# 10-de-77.net
KiCad netlist of a schematic drawn in EAGLE
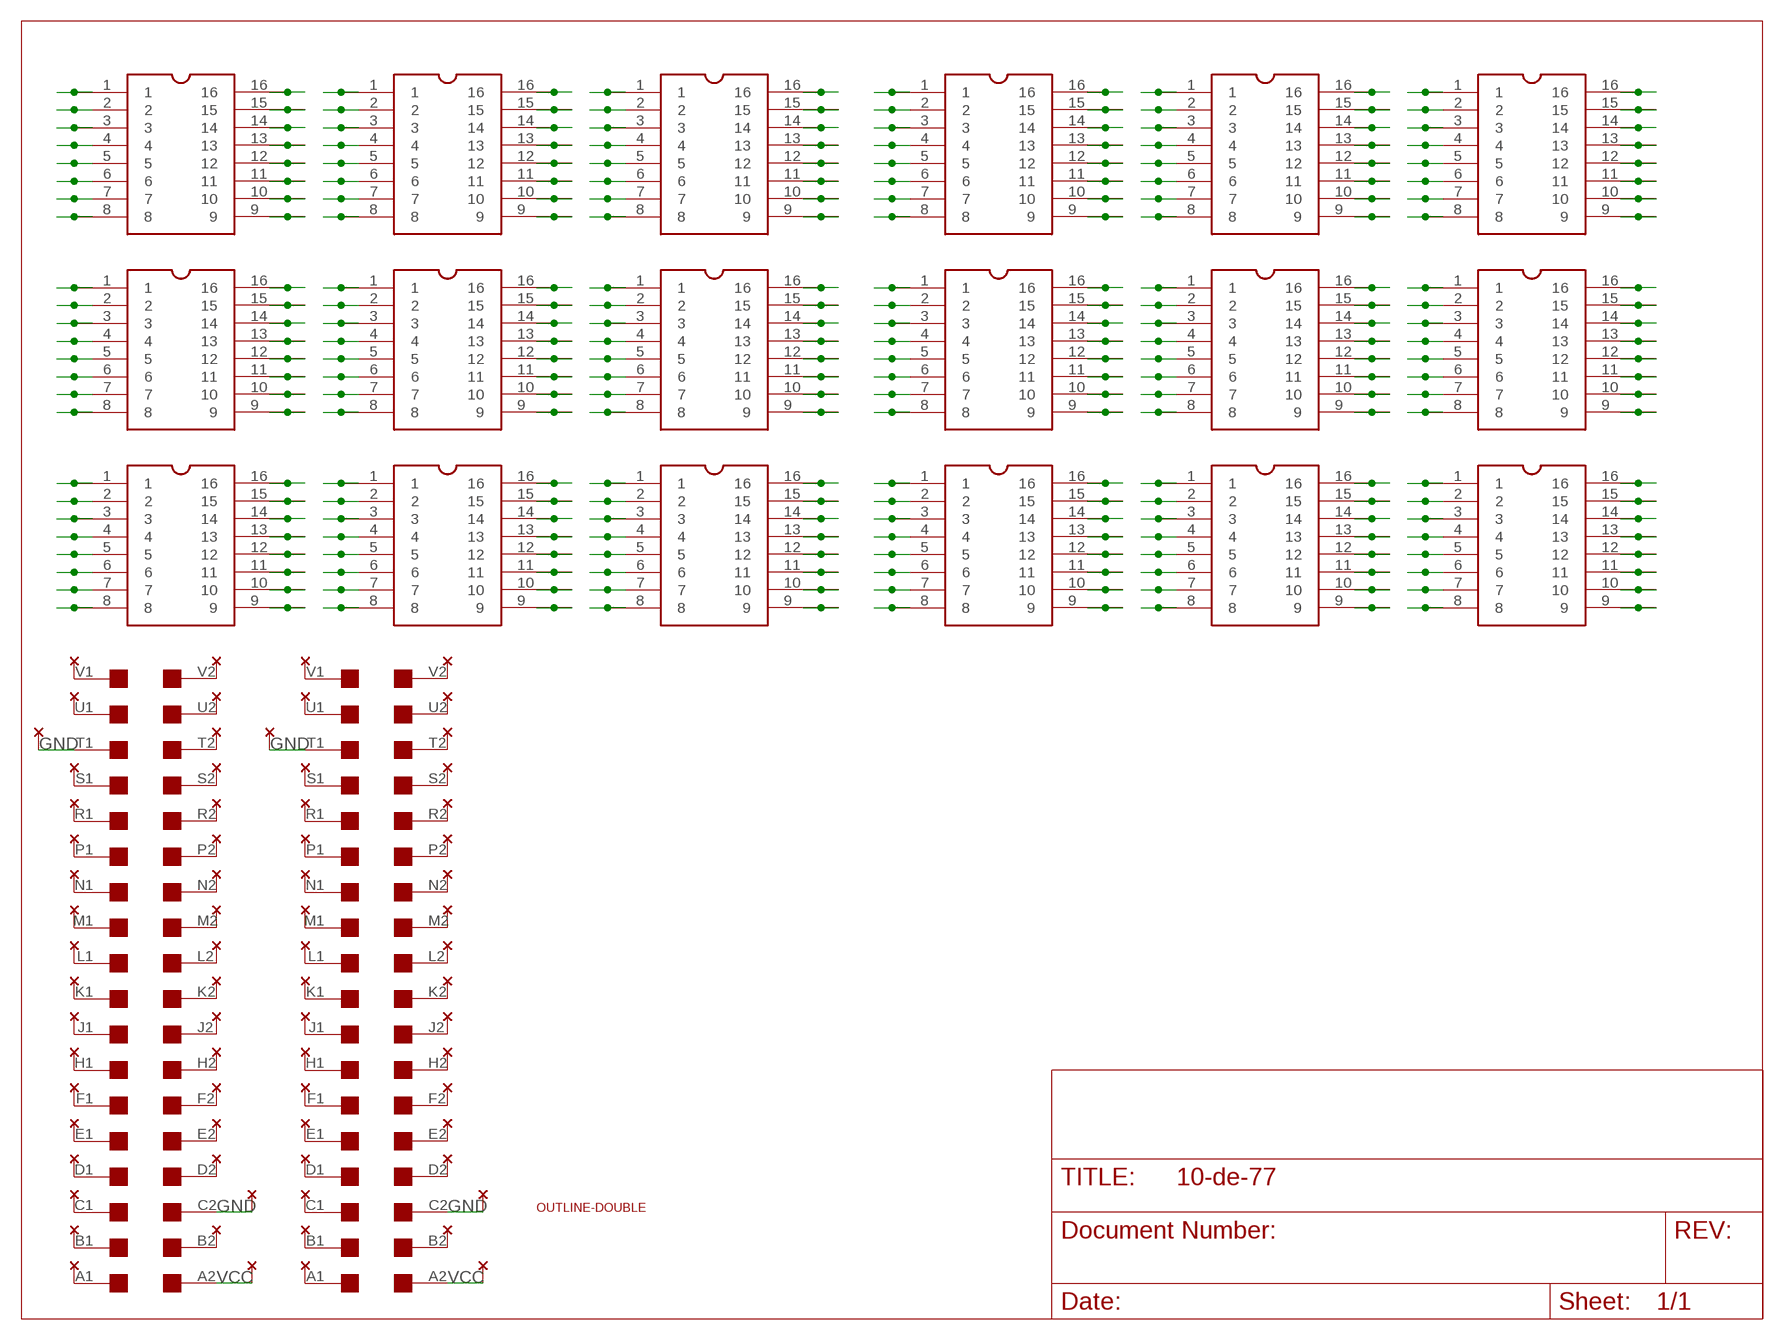
[diagram p0: schematic, sheet 1]

(export (version "E")
  (design (tool "Eeschema 10.0.6"))
  (components
    (comp (ref "U$1")
      (value "SINGLE")
      (footprint "eagle-import:EDGE-CON2")
      (libsource (lib "eagle-import") (part "SINGLE"))
    )
    (comp (ref "U$4")
      (value "OUTLINE-DOUBLE")
      (footprint "eagle-import:DOUBLE")
      (libsource (lib "eagle-import") (part "OUTLINE-DOUBLE"))
    )
    (comp (ref "U$5")
      (value "DIL16PROTO")
      (footprint "eagle-import:DIL16PROTO")
      (libsource (lib "eagle-import") (part "DIL16PROTO"))
    )
    (comp (ref "U$6")
      (value "SINGLE")
      (footprint "eagle-import:EDGE-CON2")
      (libsource (lib "eagle-import") (part "SINGLE"))
    )
    (comp (ref "U$7")
      (value "DIL16PROTO")
      (footprint "eagle-import:DIL16PROTO")
      (libsource (lib "eagle-import") (part "DIL16PROTO"))
    )
    (comp (ref "U$8")
      (value "DIL16PROTO")
      (footprint "eagle-import:DIL16PROTO")
      (libsource (lib "eagle-import") (part "DIL16PROTO"))
    )
    (comp (ref "U$9")
      (value "DIL16PROTO")
      (footprint "eagle-import:DIL16PROTO")
      (libsource (lib "eagle-import") (part "DIL16PROTO"))
    )
    (comp (ref "U$10")
      (value "DIL16PROTO")
      (footprint "eagle-import:DIL16PROTO")
      (libsource (lib "eagle-import") (part "DIL16PROTO"))
    )
    (comp (ref "U$11")
      (value "DIL16PROTO")
      (footprint "eagle-import:DIL16PROTO")
      (libsource (lib "eagle-import") (part "DIL16PROTO"))
    )
    (comp (ref "U$12")
      (value "DIL16PROTO")
      (footprint "eagle-import:DIL16PROTO")
      (libsource (lib "eagle-import") (part "DIL16PROTO"))
    )
    (comp (ref "U$13")
      (value "DIL16PROTO")
      (footprint "eagle-import:DIL16PROTO")
      (libsource (lib "eagle-import") (part "DIL16PROTO"))
    )
    (comp (ref "U$14")
      (value "DIL16PROTO")
      (footprint "eagle-import:DIL16PROTO")
      (libsource (lib "eagle-import") (part "DIL16PROTO"))
    )
    (comp (ref "U$15")
      (value "DIL16PROTO")
      (footprint "eagle-import:DIL16PROTO")
      (libsource (lib "eagle-import") (part "DIL16PROTO"))
    )
    (comp (ref "U$16")
      (value "DIL16PROTO")
      (footprint "eagle-import:DIL16PROTO")
      (libsource (lib "eagle-import") (part "DIL16PROTO"))
    )
    (comp (ref "U$17")
      (value "DIL16PROTO")
      (footprint "eagle-import:DIL16PROTO")
      (libsource (lib "eagle-import") (part "DIL16PROTO"))
    )
    (comp (ref "U$18")
      (value "DIL16PROTO")
      (footprint "eagle-import:DIL16PROTO")
      (libsource (lib "eagle-import") (part "DIL16PROTO"))
    )
    (comp (ref "U$19")
      (value "DIL16PROTO")
      (footprint "eagle-import:DIL16PROTO")
      (libsource (lib "eagle-import") (part "DIL16PROTO"))
    )
    (comp (ref "U$20")
      (value "DIL16PROTO")
      (footprint "eagle-import:DIL16PROTO")
      (libsource (lib "eagle-import") (part "DIL16PROTO"))
    )
    (comp (ref "U$21")
      (value "DIL16PROTO")
      (footprint "eagle-import:DIL16PROTO")
      (libsource (lib "eagle-import") (part "DIL16PROTO"))
    )
    (comp (ref "U$22")
      (value "DIL16PROTO")
      (footprint "eagle-import:DIL16PROTO")
      (libsource (lib "eagle-import") (part "DIL16PROTO"))
    )
    (comp (ref "U$23")
      (value "DIL16PROTO")
      (footprint "eagle-import:DIL16PROTO")
      (libsource (lib "eagle-import") (part "DIL16PROTO"))
    )
    (comp (ref "U$24")
      (value "THRU-HOLE1A")
      (footprint "eagle-import:THRU-HOLE1A")
      (libsource (lib "eagle-import") (part "THRU-HOLE1A"))
    )
    (comp (ref "U$25")
      (value "THRU-HOLE1A")
      (footprint "eagle-import:THRU-HOLE1A")
      (libsource (lib "eagle-import") (part "THRU-HOLE1A"))
    )
    (comp (ref "U$26")
      (value "THRU-HOLE1A")
      (footprint "eagle-import:THRU-HOLE1A")
      (libsource (lib "eagle-import") (part "THRU-HOLE1A"))
    )
    (comp (ref "U$27")
      (value "THRU-HOLE1A")
      (footprint "eagle-import:THRU-HOLE1A")
      (libsource (lib "eagle-import") (part "THRU-HOLE1A"))
    )
  )
  (nets
    (net (code "1") (name "/GND") (class "Default")
      (node (ref "U$1") (pin "C2") (pinfunction "1_C2") (pintype "bidirectional"))
      (node (ref "U$1") (pin "T1") (pinfunction "1_T1") (pintype "bidirectional"))
      (node (ref "U$24") (pin "T1") (pinfunction "P$1_T1") (pintype "passive"))
      (node (ref "U$25") (pin "C1") (pinfunction "P$1_C1") (pintype "passive"))
      (node (ref "U$26") (pin "T1") (pinfunction "P$1_T1") (pintype "passive"))
      (node (ref "U$27") (pin "C1") (pinfunction "P$1_C1") (pintype "passive"))
      (node (ref "U$6") (pin "C2") (pinfunction "1_C2") (pintype "bidirectional"))
      (node (ref "U$6") (pin "T1") (pinfunction "1_T1") (pintype "bidirectional"))
    )
    (net (code "2") (name "/VCC") (class "Default")
      (node (ref "U$1") (pin "A2") (pinfunction "1_A2") (pintype "bidirectional"))
      (node (ref "U$25") (pin "A1") (pinfunction "P$1_A1") (pintype "passive"))
      (node (ref "U$27") (pin "A1") (pinfunction "P$1_A1") (pintype "passive"))
      (node (ref "U$6") (pin "A2") (pinfunction "1_A2") (pintype "bidirectional"))
    )
    (net (code "3") (name "Net-(U$1A-1)") (class "Default")
      (node (ref "U$1") (pin "A1") (pinfunction "1_A1") (pintype "bidirectional"))
      (node (ref "U$24") (pin "A1") (pinfunction "P$1_A1") (pintype "passive"))
    )
    (net (code "4") (name "Net-(U$1AA-1)") (class "Default")
      (node (ref "U$1") (pin "R1") (pinfunction "1_R1") (pintype "bidirectional"))
      (node (ref "U$24") (pin "R1") (pinfunction "P$1_R1") (pintype "passive"))
    )
    (net (code "5") (name "Net-(U$1AB-1)") (class "Default")
      (node (ref "U$1") (pin "R2") (pinfunction "1_R2") (pintype "bidirectional"))
      (node (ref "U$25") (pin "R1") (pinfunction "P$1_R1") (pintype "passive"))
    )
    (net (code "6") (name "Net-(U$1AC-1)") (class "Default")
      (node (ref "U$1") (pin "S1") (pinfunction "1_S1") (pintype "bidirectional"))
      (node (ref "U$24") (pin "S1") (pinfunction "P$1_S1") (pintype "passive"))
    )
    (net (code "7") (name "Net-(U$1AD-1)") (class "Default")
      (node (ref "U$1") (pin "S2") (pinfunction "1_S2") (pintype "bidirectional"))
      (node (ref "U$25") (pin "S1") (pinfunction "P$1_S1") (pintype "passive"))
    )
    (net (code "8") (name "Net-(U$1AF-1)") (class "Default")
      (node (ref "U$1") (pin "T2") (pinfunction "1_T2") (pintype "bidirectional"))
      (node (ref "U$25") (pin "T1") (pinfunction "P$1_T1") (pintype "passive"))
    )
    (net (code "9") (name "Net-(U$1AG-1)") (class "Default")
      (node (ref "U$1") (pin "U1") (pinfunction "1_U1") (pintype "bidirectional"))
      (node (ref "U$24") (pin "U1") (pinfunction "P$1_U1") (pintype "passive"))
    )
    (net (code "10") (name "Net-(U$1AH-1)") (class "Default")
      (node (ref "U$1") (pin "U2") (pinfunction "1_U2") (pintype "bidirectional"))
      (node (ref "U$25") (pin "U1") (pinfunction "P$1_U1") (pintype "passive"))
    )
    (net (code "11") (name "Net-(U$1AI-1)") (class "Default")
      (node (ref "U$1") (pin "V1") (pinfunction "1_V1") (pintype "bidirectional"))
      (node (ref "U$24") (pin "V1") (pinfunction "P$1_V1") (pintype "passive"))
    )
    (net (code "12") (name "Net-(U$1AJ-1)") (class "Default")
      (node (ref "U$1") (pin "V2") (pinfunction "1_V2") (pintype "bidirectional"))
      (node (ref "U$25") (pin "V1") (pinfunction "P$1_V1") (pintype "passive"))
    )
    (net (code "13") (name "Net-(U$1C-1)") (class "Default")
      (node (ref "U$1") (pin "B1") (pinfunction "1_B1") (pintype "bidirectional"))
      (node (ref "U$24") (pin "B1") (pinfunction "P$1_B1") (pintype "passive"))
    )
    (net (code "14") (name "Net-(U$1D-1)") (class "Default")
      (node (ref "U$1") (pin "B2") (pinfunction "1_B2") (pintype "bidirectional"))
      (node (ref "U$25") (pin "B1") (pinfunction "P$1_B1") (pintype "passive"))
    )
    (net (code "15") (name "Net-(U$1E-1)") (class "Default")
      (node (ref "U$1") (pin "C1") (pinfunction "1_C1") (pintype "bidirectional"))
      (node (ref "U$24") (pin "C1") (pinfunction "P$1_C1") (pintype "passive"))
    )
    (net (code "16") (name "Net-(U$1G-1)") (class "Default")
      (node (ref "U$1") (pin "D1") (pinfunction "1_D1") (pintype "bidirectional"))
      (node (ref "U$24") (pin "D1") (pinfunction "P$1_D1") (pintype "passive"))
    )
    (net (code "17") (name "Net-(U$1H-1)") (class "Default")
      (node (ref "U$1") (pin "D2") (pinfunction "1_D2") (pintype "bidirectional"))
      (node (ref "U$25") (pin "D1") (pinfunction "P$1_D1") (pintype "passive"))
    )
    (net (code "18") (name "Net-(U$1I-1)") (class "Default")
      (node (ref "U$1") (pin "E1") (pinfunction "1_E1") (pintype "bidirectional"))
      (node (ref "U$24") (pin "E1") (pinfunction "P$1_E1") (pintype "passive"))
    )
    (net (code "19") (name "Net-(U$1J-1)") (class "Default")
      (node (ref "U$1") (pin "E2") (pinfunction "1_E2") (pintype "bidirectional"))
      (node (ref "U$25") (pin "E1") (pinfunction "P$1_E1") (pintype "passive"))
    )
    (net (code "20") (name "Net-(U$1K-1)") (class "Default")
      (node (ref "U$1") (pin "F1") (pinfunction "1_F1") (pintype "bidirectional"))
      (node (ref "U$24") (pin "F1") (pinfunction "P$1_F1") (pintype "passive"))
    )
    (net (code "21") (name "Net-(U$1L-1)") (class "Default")
      (node (ref "U$1") (pin "F2") (pinfunction "1_F2") (pintype "bidirectional"))
      (node (ref "U$25") (pin "F1") (pinfunction "P$1_F1") (pintype "passive"))
    )
    (net (code "22") (name "Net-(U$1M-1)") (class "Default")
      (node (ref "U$1") (pin "H1") (pinfunction "1_H1") (pintype "bidirectional"))
      (node (ref "U$24") (pin "H1") (pinfunction "P$1_H1") (pintype "passive"))
    )
    (net (code "23") (name "Net-(U$1N-1)") (class "Default")
      (node (ref "U$1") (pin "H2") (pinfunction "1_H2") (pintype "bidirectional"))
      (node (ref "U$25") (pin "H1") (pinfunction "P$1_H1") (pintype "passive"))
    )
    (net (code "24") (name "Net-(U$1O-1)") (class "Default")
      (node (ref "U$1") (pin "J1") (pinfunction "1_J1") (pintype "bidirectional"))
      (node (ref "U$24") (pin "J1") (pinfunction "P$1_J1") (pintype "passive"))
    )
    (net (code "25") (name "Net-(U$1P-1)") (class "Default")
      (node (ref "U$1") (pin "J2") (pinfunction "1_J2") (pintype "bidirectional"))
      (node (ref "U$25") (pin "J1") (pinfunction "P$1_J1") (pintype "passive"))
    )
    (net (code "26") (name "Net-(U$1Q-1)") (class "Default")
      (node (ref "U$1") (pin "K1") (pinfunction "1_K1") (pintype "bidirectional"))
      (node (ref "U$24") (pin "K1") (pinfunction "P$1_K1") (pintype "passive"))
    )
    (net (code "27") (name "Net-(U$1R-1)") (class "Default")
      (node (ref "U$1") (pin "K2") (pinfunction "1_K2") (pintype "bidirectional"))
      (node (ref "U$25") (pin "K1") (pinfunction "P$1_K1") (pintype "passive"))
    )
    (net (code "28") (name "Net-(U$1S-1)") (class "Default")
      (node (ref "U$1") (pin "L1") (pinfunction "1_L1") (pintype "bidirectional"))
      (node (ref "U$24") (pin "L1") (pinfunction "P$1_L1") (pintype "passive"))
    )
    (net (code "29") (name "Net-(U$1T-1)") (class "Default")
      (node (ref "U$1") (pin "L2") (pinfunction "1_L2") (pintype "bidirectional"))
      (node (ref "U$25") (pin "L1") (pinfunction "P$1_L1") (pintype "passive"))
    )
    (net (code "30") (name "Net-(U$1U-1)") (class "Default")
      (node (ref "U$1") (pin "M1") (pinfunction "1_M1") (pintype "bidirectional"))
      (node (ref "U$24") (pin "M1") (pinfunction "P$1_M1") (pintype "passive"))
    )
    (net (code "31") (name "Net-(U$1V-1)") (class "Default")
      (node (ref "U$1") (pin "M2") (pinfunction "1_M2") (pintype "bidirectional"))
      (node (ref "U$25") (pin "M1") (pinfunction "P$1_M1") (pintype "passive"))
    )
    (net (code "32") (name "Net-(U$1W-1)") (class "Default")
      (node (ref "U$1") (pin "N1") (pinfunction "1_N1") (pintype "bidirectional"))
      (node (ref "U$24") (pin "N1") (pinfunction "P$1_N1") (pintype "passive"))
    )
    (net (code "33") (name "Net-(U$1X-1)") (class "Default")
      (node (ref "U$1") (pin "N2") (pinfunction "1_N2") (pintype "bidirectional"))
      (node (ref "U$25") (pin "N1") (pinfunction "P$1_N1") (pintype "passive"))
    )
    (net (code "34") (name "Net-(U$1Y-1)") (class "Default")
      (node (ref "U$1") (pin "P1") (pinfunction "1_P1") (pintype "bidirectional"))
      (node (ref "U$24") (pin "P1") (pinfunction "P$1_P1") (pintype "passive"))
    )
    (net (code "35") (name "Net-(U$1Z-1)") (class "Default")
      (node (ref "U$1") (pin "P2") (pinfunction "1_P2") (pintype "bidirectional"))
      (node (ref "U$25") (pin "P1") (pinfunction "P$1_P1") (pintype "passive"))
    )
    (net (code "36") (name "Net-(U$5-1-Pad1@2)") (class "Default")
      (node (ref "U$5") (pin "1") (pinfunction "1_1") (pintype "passive"))
      (node (ref "U$5") (pin "1@2") (pinfunction "1_1@2") (pintype "passive"))
      (node (ref "U$5") (pin "1@3") (pinfunction "1_1@3") (pintype "passive"))
    )
    (net (code "37") (name "Net-(U$5-2-Pad2@2)") (class "Default")
      (node (ref "U$5") (pin "2") (pinfunction "2_2") (pintype "passive"))
      (node (ref "U$5") (pin "2@2") (pinfunction "2_2@2") (pintype "passive"))
      (node (ref "U$5") (pin "2@3") (pinfunction "2_2@3") (pintype "passive"))
    )
    (net (code "38") (name "Net-(U$5-3-Pad3@2)") (class "Default")
      (node (ref "U$5") (pin "3") (pinfunction "3_3") (pintype "passive"))
      (node (ref "U$5") (pin "3@2") (pinfunction "3_3@2") (pintype "passive"))
      (node (ref "U$5") (pin "3@3") (pinfunction "3_3@3") (pintype "passive"))
    )
    (net (code "39") (name "Net-(U$5-4-Pad4@2)") (class "Default")
      (node (ref "U$5") (pin "4") (pinfunction "4_4") (pintype "passive"))
      (node (ref "U$5") (pin "4@2") (pinfunction "4_4@2") (pintype "passive"))
      (node (ref "U$5") (pin "4@3") (pinfunction "4_4@3") (pintype "passive"))
    )
    (net (code "40") (name "Net-(U$5-5-Pad5@2)") (class "Default")
      (node (ref "U$5") (pin "5") (pinfunction "5_5") (pintype "passive"))
      (node (ref "U$5") (pin "5@2") (pinfunction "5_5@2") (pintype "passive"))
      (node (ref "U$5") (pin "5@3") (pinfunction "5_5@3") (pintype "passive"))
    )
    (net (code "41") (name "Net-(U$5-6-Pad6@2)") (class "Default")
      (node (ref "U$5") (pin "6") (pinfunction "6_6") (pintype "passive"))
      (node (ref "U$5") (pin "6@2") (pinfunction "6_6@2") (pintype "passive"))
      (node (ref "U$5") (pin "6@3") (pinfunction "6_6@3") (pintype "passive"))
    )
    (net (code "42") (name "Net-(U$5-7-Pad7@2)") (class "Default")
      (node (ref "U$5") (pin "7") (pinfunction "7_7") (pintype "passive"))
      (node (ref "U$5") (pin "7@2") (pinfunction "7_7@2") (pintype "passive"))
      (node (ref "U$5") (pin "7@3") (pinfunction "7_7@3") (pintype "passive"))
    )
    (net (code "43") (name "Net-(U$5-8-Pad8@2)") (class "Default")
      (node (ref "U$5") (pin "8") (pinfunction "8_8") (pintype "passive"))
      (node (ref "U$5") (pin "8@2") (pinfunction "8_8@2") (pintype "passive"))
      (node (ref "U$5") (pin "8@3") (pinfunction "8_8@3") (pintype "passive"))
    )
    (net (code "44") (name "Net-(U$5-9-Pad9@2)") (class "Default")
      (node (ref "U$5") (pin "9") (pinfunction "9_9") (pintype "passive"))
      (node (ref "U$5") (pin "9@2") (pinfunction "9_9@2") (pintype "passive"))
      (node (ref "U$5") (pin "9@3") (pinfunction "9_9@3") (pintype "passive"))
    )
    (net (code "45") (name "Net-(U$5-10-Pad10@2)") (class "Default")
      (node (ref "U$5") (pin "10") (pinfunction "10_10") (pintype "passive"))
      (node (ref "U$5") (pin "10@2") (pinfunction "10_10@2") (pintype "passive"))
      (node (ref "U$5") (pin "10@3") (pinfunction "10_10@3") (pintype "passive"))
    )
    (net (code "46") (name "Net-(U$5-11-Pad11@2)") (class "Default")
      (node (ref "U$5") (pin "11") (pinfunction "11_11") (pintype "passive"))
      (node (ref "U$5") (pin "11@2") (pinfunction "11_11@2") (pintype "passive"))
      (node (ref "U$5") (pin "11@3") (pinfunction "11_11@3") (pintype "passive"))
    )
    (net (code "47") (name "Net-(U$5-12-Pad12@2)") (class "Default")
      (node (ref "U$5") (pin "12") (pinfunction "12_12") (pintype "passive"))
      (node (ref "U$5") (pin "12@2") (pinfunction "12_12@2") (pintype "passive"))
      (node (ref "U$5") (pin "12@3") (pinfunction "12_12@3") (pintype "passive"))
    )
    (net (code "48") (name "Net-(U$5-13-Pad13@2)") (class "Default")
      (node (ref "U$5") (pin "13") (pinfunction "13_13") (pintype "passive"))
      (node (ref "U$5") (pin "13@2") (pinfunction "13_13@2") (pintype "passive"))
      (node (ref "U$5") (pin "13@3") (pinfunction "13_13@3") (pintype "passive"))
    )
    (net (code "49") (name "Net-(U$5-14-Pad14@2)") (class "Default")
      (node (ref "U$5") (pin "14") (pinfunction "14_14") (pintype "passive"))
      (node (ref "U$5") (pin "14@2") (pinfunction "14_14@2") (pintype "passive"))
      (node (ref "U$5") (pin "14@3") (pinfunction "14_14@3") (pintype "passive"))
    )
    (net (code "50") (name "Net-(U$5-15-Pad15@2)") (class "Default")
      (node (ref "U$5") (pin "15") (pinfunction "15_15") (pintype "passive"))
      (node (ref "U$5") (pin "15@2") (pinfunction "15_15@2") (pintype "passive"))
      (node (ref "U$5") (pin "15@3") (pinfunction "15_15@3") (pintype "passive"))
    )
    (net (code "51") (name "Net-(U$5-16-Pad16@2)") (class "Default")
      (node (ref "U$5") (pin "16") (pinfunction "16_16") (pintype "passive"))
      (node (ref "U$5") (pin "16@2") (pinfunction "16_16@2") (pintype "passive"))
      (node (ref "U$5") (pin "16@3") (pinfunction "16_16@3") (pintype "passive"))
    )
    (net (code "52") (name "Net-(U$7-1-Pad1@2)") (class "Default")
      (node (ref "U$7") (pin "1") (pinfunction "1_1") (pintype "passive"))
      (node (ref "U$7") (pin "1@2") (pinfunction "1_1@2") (pintype "passive"))
      (node (ref "U$7") (pin "1@3") (pinfunction "1_1@3") (pintype "passive"))
    )
    (net (code "53") (name "Net-(U$7-2-Pad2@2)") (class "Default")
      (node (ref "U$7") (pin "2") (pinfunction "2_2") (pintype "passive"))
      (node (ref "U$7") (pin "2@2") (pinfunction "2_2@2") (pintype "passive"))
      (node (ref "U$7") (pin "2@3") (pinfunction "2_2@3") (pintype "passive"))
    )
    (net (code "54") (name "Net-(U$7-3-Pad3@2)") (class "Default")
      (node (ref "U$7") (pin "3") (pinfunction "3_3") (pintype "passive"))
      (node (ref "U$7") (pin "3@2") (pinfunction "3_3@2") (pintype "passive"))
      (node (ref "U$7") (pin "3@3") (pinfunction "3_3@3") (pintype "passive"))
    )
    (net (code "55") (name "Net-(U$7-4-Pad4@2)") (class "Default")
      (node (ref "U$7") (pin "4") (pinfunction "4_4") (pintype "passive"))
      (node (ref "U$7") (pin "4@2") (pinfunction "4_4@2") (pintype "passive"))
      (node (ref "U$7") (pin "4@3") (pinfunction "4_4@3") (pintype "passive"))
    )
    (net (code "56") (name "Net-(U$7-5-Pad5@2)") (class "Default")
      (node (ref "U$7") (pin "5") (pinfunction "5_5") (pintype "passive"))
      (node (ref "U$7") (pin "5@2") (pinfunction "5_5@2") (pintype "passive"))
      (node (ref "U$7") (pin "5@3") (pinfunction "5_5@3") (pintype "passive"))
    )
    (net (code "57") (name "Net-(U$7-6-Pad6@2)") (class "Default")
      (node (ref "U$7") (pin "6") (pinfunction "6_6") (pintype "passive"))
      (node (ref "U$7") (pin "6@2") (pinfunction "6_6@2") (pintype "passive"))
      (node (ref "U$7") (pin "6@3") (pinfunction "6_6@3") (pintype "passive"))
    )
    (net (code "58") (name "Net-(U$7-7-Pad7@2)") (class "Default")
      (node (ref "U$7") (pin "7") (pinfunction "7_7") (pintype "passive"))
      (node (ref "U$7") (pin "7@2") (pinfunction "7_7@2") (pintype "passive"))
      (node (ref "U$7") (pin "7@3") (pinfunction "7_7@3") (pintype "passive"))
    )
    (net (code "59") (name "Net-(U$7-8-Pad8@2)") (class "Default")
      (node (ref "U$7") (pin "8") (pinfunction "8_8") (pintype "passive"))
      (node (ref "U$7") (pin "8@2") (pinfunction "8_8@2") (pintype "passive"))
      (node (ref "U$7") (pin "8@3") (pinfunction "8_8@3") (pintype "passive"))
    )
    (net (code "60") (name "Net-(U$7-9-Pad9@2)") (class "Default")
      (node (ref "U$7") (pin "9") (pinfunction "9_9") (pintype "passive"))
      (node (ref "U$7") (pin "9@2") (pinfunction "9_9@2") (pintype "passive"))
      (node (ref "U$7") (pin "9@3") (pinfunction "9_9@3") (pintype "passive"))
    )
    (net (code "61") (name "Net-(U$7-10-Pad10@2)") (class "Default")
      (node (ref "U$7") (pin "10") (pinfunction "10_10") (pintype "passive"))
      (node (ref "U$7") (pin "10@2") (pinfunction "10_10@2") (pintype "passive"))
      (node (ref "U$7") (pin "10@3") (pinfunction "10_10@3") (pintype "passive"))
    )
    (net (code "62") (name "Net-(U$7-11-Pad11@2)") (class "Default")
      (node (ref "U$7") (pin "11") (pinfunction "11_11") (pintype "passive"))
      (node (ref "U$7") (pin "11@2") (pinfunction "11_11@2") (pintype "passive"))
      (node (ref "U$7") (pin "11@3") (pinfunction "11_11@3") (pintype "passive"))
    )
    (net (code "63") (name "Net-(U$7-12-Pad12@2)") (class "Default")
      (node (ref "U$7") (pin "12") (pinfunction "12_12") (pintype "passive"))
      (node (ref "U$7") (pin "12@2") (pinfunction "12_12@2") (pintype "passive"))
      (node (ref "U$7") (pin "12@3") (pinfunction "12_12@3") (pintype "passive"))
    )
    (net (code "64") (name "Net-(U$7-13-Pad13@2)") (class "Default")
      (node (ref "U$7") (pin "13") (pinfunction "13_13") (pintype "passive"))
      (node (ref "U$7") (pin "13@2") (pinfunction "13_13@2") (pintype "passive"))
      (node (ref "U$7") (pin "13@3") (pinfunction "13_13@3") (pintype "passive"))
    )
    (net (code "65") (name "Net-(U$7-14-Pad14@2)") (class "Default")
      (node (ref "U$7") (pin "14") (pinfunction "14_14") (pintype "passive"))
      (node (ref "U$7") (pin "14@2") (pinfunction "14_14@2") (pintype "passive"))
      (node (ref "U$7") (pin "14@3") (pinfunction "14_14@3") (pintype "passive"))
    )
    (net (code "66") (name "Net-(U$7-15-Pad15@2)") (class "Default")
      (node (ref "U$7") (pin "15") (pinfunction "15_15") (pintype "passive"))
      (node (ref "U$7") (pin "15@2") (pinfunction "15_15@2") (pintype "passive"))
      (node (ref "U$7") (pin "15@3") (pinfunction "15_15@3") (pintype "passive"))
    )
    (net (code "67") (name "Net-(U$7-16-Pad16@2)") (class "Default")
      (node (ref "U$7") (pin "16") (pinfunction "16_16") (pintype "passive"))
      (node (ref "U$7") (pin "16@2") (pinfunction "16_16@2") (pintype "passive"))
      (node (ref "U$7") (pin "16@3") (pinfunction "16_16@3") (pintype "passive"))
    )
    (net (code "68") (name "Net-(U$8-1-Pad1@2)") (class "Default")
      (node (ref "U$8") (pin "1") (pinfunction "1_1") (pintype "passive"))
      (node (ref "U$8") (pin "1@2") (pinfunction "1_1@2") (pintype "passive"))
      (node (ref "U$8") (pin "1@3") (pinfunction "1_1@3") (pintype "passive"))
    )
    (net (code "69") (name "Net-(U$8-2-Pad2@2)") (class "Default")
      (node (ref "U$8") (pin "2") (pinfunction "2_2") (pintype "passive"))
      (node (ref "U$8") (pin "2@2") (pinfunction "2_2@2") (pintype "passive"))
      (node (ref "U$8") (pin "2@3") (pinfunction "2_2@3") (pintype "passive"))
    )
    (net (code "70") (name "Net-(U$8-3-Pad3@2)") (class "Default")
      (node (ref "U$8") (pin "3") (pinfunction "3_3") (pintype "passive"))
      (node (ref "U$8") (pin "3@2") (pinfunction "3_3@2") (pintype "passive"))
      (node (ref "U$8") (pin "3@3") (pinfunction "3_3@3") (pintype "passive"))
    )
    (net (code "71") (name "Net-(U$8-4-Pad4@2)") (class "Default")
      (node (ref "U$8") (pin "4") (pinfunction "4_4") (pintype "passive"))
      (node (ref "U$8") (pin "4@2") (pinfunction "4_4@2") (pintype "passive"))
      (node (ref "U$8") (pin "4@3") (pinfunction "4_4@3") (pintype "passive"))
    )
    (net (code "72") (name "Net-(U$8-5-Pad5@2)") (class "Default")
      (node (ref "U$8") (pin "5") (pinfunction "5_5") (pintype "passive"))
      (node (ref "U$8") (pin "5@2") (pinfunction "5_5@2") (pintype "passive"))
      (node (ref "U$8") (pin "5@3") (pinfunction "5_5@3") (pintype "passive"))
    )
    (net (code "73") (name "Net-(U$8-6-Pad6@2)") (class "Default")
      (node (ref "U$8") (pin "6") (pinfunction "6_6") (pintype "passive"))
      (node (ref "U$8") (pin "6@2") (pinfunction "6_6@2") (pintype "passive"))
      (node (ref "U$8") (pin "6@3") (pinfunction "6_6@3") (pintype "passive"))
    )
    (net (code "74") (name "Net-(U$8-7-Pad7@2)") (class "Default")
      (node (ref "U$8") (pin "7") (pinfunction "7_7") (pintype "passive"))
      (node (ref "U$8") (pin "7@2") (pinfunction "7_7@2") (pintype "passive"))
      (node (ref "U$8") (pin "7@3") (pinfunction "7_7@3") (pintype "passive"))
    )
    (net (code "75") (name "Net-(U$8-8-Pad8@2)") (class "Default")
      (node (ref "U$8") (pin "8") (pinfunction "8_8") (pintype "passive"))
      (node (ref "U$8") (pin "8@2") (pinfunction "8_8@2") (pintype "passive"))
      (node (ref "U$8") (pin "8@3") (pinfunction "8_8@3") (pintype "passive"))
    )
    (net (code "76") (name "Net-(U$8-9-Pad9@2)") (class "Default")
      (node (ref "U$8") (pin "9") (pinfunction "9_9") (pintype "passive"))
      (node (ref "U$8") (pin "9@2") (pinfunction "9_9@2") (pintype "passive"))
      (node (ref "U$8") (pin "9@3") (pinfunction "9_9@3") (pintype "passive"))
    )
    (net (code "77") (name "Net-(U$8-10-Pad10@2)") (class "Default")
      (node (ref "U$8") (pin "10") (pinfunction "10_10") (pintype "passive"))
      (node (ref "U$8") (pin "10@2") (pinfunction "10_10@2") (pintype "passive"))
      (node (ref "U$8") (pin "10@3") (pinfunction "10_10@3") (pintype "passive"))
    )
    (net (code "78") (name "Net-(U$8-11-Pad11@2)") (class "Default")
      (node (ref "U$8") (pin "11") (pinfunction "11_11") (pintype "passive"))
      (node (ref "U$8") (pin "11@2") (pinfunction "11_11@2") (pintype "passive"))
      (node (ref "U$8") (pin "11@3") (pinfunction "11_11@3") (pintype "passive"))
    )
    (net (code "79") (name "Net-(U$8-12-Pad12@2)") (class "Default")
      (node (ref "U$8") (pin "12") (pinfunction "12_12") (pintype "passive"))
      (node (ref "U$8") (pin "12@2") (pinfunction "12_12@2") (pintype "passive"))
      (node (ref "U$8") (pin "12@3") (pinfunction "12_12@3") (pintype "passive"))
    )
    (net (code "80") (name "Net-(U$8-13-Pad13@2)") (class "Default")
      (node (ref "U$8") (pin "13") (pinfunction "13_13") (pintype "passive"))
      (node (ref "U$8") (pin "13@2") (pinfunction "13_13@2") (pintype "passive"))
      (node (ref "U$8") (pin "13@3") (pinfunction "13_13@3") (pintype "passive"))
    )
    (net (code "81") (name "Net-(U$8-14-Pad14@2)") (class "Default")
      (node (ref "U$8") (pin "14") (pinfunction "14_14") (pintype "passive"))
      (node (ref "U$8") (pin "14@2") (pinfunction "14_14@2") (pintype "passive"))
      (node (ref "U$8") (pin "14@3") (pinfunction "14_14@3") (pintype "passive"))
    )
    (net (code "82") (name "Net-(U$8-15-Pad15@2)") (class "Default")
      (node (ref "U$8") (pin "15") (pinfunction "15_15") (pintype "passive"))
      (node (ref "U$8") (pin "15@2") (pinfunction "15_15@2") (pintype "passive"))
      (node (ref "U$8") (pin "15@3") (pinfunction "15_15@3") (pintype "passive"))
    )
    (net (code "83") (name "Net-(U$8-16-Pad16@2)") (class "Default")
      (node (ref "U$8") (pin "16") (pinfunction "16_16") (pintype "passive"))
      (node (ref "U$8") (pin "16@2") (pinfunction "16_16@2") (pintype "passive"))
      (node (ref "U$8") (pin "16@3") (pinfunction "16_16@3") (pintype "passive"))
    )
    (net (code "84") (name "Net-(U$9-1-Pad1@2)") (class "Default")
      (node (ref "U$9") (pin "1") (pinfunction "1_1") (pintype "passive"))
      (node (ref "U$9") (pin "1@2") (pinfunction "1_1@2") (pintype "passive"))
      (node (ref "U$9") (pin "1@3") (pinfunction "1_1@3") (pintype "passive"))
    )
    (net (code "85") (name "Net-(U$9-2-Pad2@2)") (class "Default")
      (node (ref "U$9") (pin "2") (pinfunction "2_2") (pintype "passive"))
      (node (ref "U$9") (pin "2@2") (pinfunction "2_2@2") (pintype "passive"))
      (node (ref "U$9") (pin "2@3") (pinfunction "2_2@3") (pintype "passive"))
    )
    (net (code "86") (name "Net-(U$9-3-Pad3@2)") (class "Default")
      (node (ref "U$9") (pin "3") (pinfunction "3_3") (pintype "passive"))
      (node (ref "U$9") (pin "3@2") (pinfunction "3_3@2") (pintype "passive"))
      (node (ref "U$9") (pin "3@3") (pinfunction "3_3@3") (pintype "passive"))
    )
    (net (code "87") (name "Net-(U$9-4-Pad4@2)") (class "Default")
      (node (ref "U$9") (pin "4") (pinfunction "4_4") (pintype "passive"))
      (node (ref "U$9") (pin "4@2") (pinfunction "4_4@2") (pintype "passive"))
      (node (ref "U$9") (pin "4@3") (pinfunction "4_4@3") (pintype "passive"))
    )
    (net (code "88") (name "Net-(U$9-5-Pad5@2)") (class "Default")
      (node (ref "U$9") (pin "5") (pinfunction "5_5") (pintype "passive"))
      (node (ref "U$9") (pin "5@2") (pinfunction "5_5@2") (pintype "passive"))
      (node (ref "U$9") (pin "5@3") (pinfunction "5_5@3") (pintype "passive"))
    )
    (net (code "89") (name "Net-(U$9-6-Pad6@2)") (class "Default")
      (node (ref "U$9") (pin "6") (pinfunction "6_6") (pintype "passive"))
      (node (ref "U$9") (pin "6@2") (pinfunction "6_6@2") (pintype "passive"))
      (node (ref "U$9") (pin "6@3") (pinfunction "6_6@3") (pintype "passive"))
    )
    (net (code "90") (name "Net-(U$9-7-Pad7@2)") (class "Default")
      (node (ref "U$9") (pin "7") (pinfunction "7_7") (pintype "passive"))
      (node (ref "U$9") (pin "7@2") (pinfunction "7_7@2") (pintype "passive"))
      (node (ref "U$9") (pin "7@3") (pinfunction "7_7@3") (pintype "passive"))
    )
    (net (code "91") (name "Net-(U$9-8-Pad8@2)") (class "Default")
      (node (ref "U$9") (pin "8") (pinfunction "8_8") (pintype "passive"))
      (node (ref "U$9") (pin "8@2") (pinfunction "8_8@2") (pintype "passive"))
      (node (ref "U$9") (pin "8@3") (pinfunction "8_8@3") (pintype "passive"))
    )
    (net (code "92") (name "Net-(U$9-9-Pad9@2)") (class "Default")
      (node (ref "U$9") (pin "9") (pinfunction "9_9") (pintype "passive"))
      (node (ref "U$9") (pin "9@2") (pinfunction "9_9@2") (pintype "passive"))
      (node (ref "U$9") (pin "9@3") (pinfunction "9_9@3") (pintype "passive"))
    )
    (net (code "93") (name "Net-(U$9-10-Pad10@2)") (class "Default")
      (node (ref "U$9") (pin "10") (pinfunction "10_10") (pintype "passive"))
      (node (ref "U$9") (pin "10@2") (pinfunction "10_10@2") (pintype "passive"))
      (node (ref "U$9") (pin "10@3") (pinfunction "10_10@3") (pintype "passive"))
    )
    (net (code "94") (name "Net-(U$9-11-Pad11@2)") (class "Default")
      (node (ref "U$9") (pin "11") (pinfunction "11_11") (pintype "passive"))
      (node (ref "U$9") (pin "11@2") (pinfunction "11_11@2") (pintype "passive"))
      (node (ref "U$9") (pin "11@3") (pinfunction "11_11@3") (pintype "passive"))
    )
    (net (code "95") (name "Net-(U$9-12-Pad12@2)") (class "Default")
      (node (ref "U$9") (pin "12") (pinfunction "12_12") (pintype "passive"))
      (node (ref "U$9") (pin "12@2") (pinfunction "12_12@2") (pintype "passive"))
      (node (ref "U$9") (pin "12@3") (pinfunction "12_12@3") (pintype "passive"))
    )
    (net (code "96") (name "Net-(U$9-13-Pad13@2)") (class "Default")
      (node (ref "U$9") (pin "13") (pinfunction "13_13") (pintype "passive"))
      (node (ref "U$9") (pin "13@2") (pinfunction "13_13@2") (pintype "passive"))
      (node (ref "U$9") (pin "13@3") (pinfunction "13_13@3") (pintype "passive"))
    )
    (net (code "97") (name "Net-(U$9-14-Pad14@2)") (class "Default")
      (node (ref "U$9") (pin "14") (pinfunction "14_14") (pintype "passive"))
      (node (ref "U$9") (pin "14@2") (pinfunction "14_14@2") (pintype "passive"))
      (node (ref "U$9") (pin "14@3") (pinfunction "14_14@3") (pintype "passive"))
    )
    (net (code "98") (name "Net-(U$9-15-Pad15@2)") (class "Default")
      (node (ref "U$9") (pin "15") (pinfunction "15_15") (pintype "passive"))
      (node (ref "U$9") (pin "15@2") (pinfunction "15_15@2") (pintype "passive"))
      (node (ref "U$9") (pin "15@3") (pinfunction "15_15@3") (pintype "passive"))
    )
    (net (code "99") (name "Net-(U$9-16-Pad16@2)") (class "Default")
      (node (ref "U$9") (pin "16") (pinfunction "16_16") (pintype "passive"))
      (node (ref "U$9") (pin "16@2") (pinfunction "16_16@2") (pintype "passive"))
      (node (ref "U$9") (pin "16@3") (pinfunction "16_16@3") (pintype "passive"))
    )
    (net (code "100") (name "Net-(U$10-1-Pad1@2)") (class "Default")
      (node (ref "U$10") (pin "1") (pinfunction "1_1") (pintype "passive"))
      (node (ref "U$10") (pin "1@2") (pinfunction "1_1@2") (pintype "passive"))
      (node (ref "U$10") (pin "1@3") (pinfunction "1_1@3") (pintype "passive"))
    )
    (net (code "101") (name "Net-(U$10-2-Pad2@2)") (class "Default")
      (node (ref "U$10") (pin "2") (pinfunction "2_2") (pintype "passive"))
      (node (ref "U$10") (pin "2@2") (pinfunction "2_2@2") (pintype "passive"))
      (node (ref "U$10") (pin "2@3") (pinfunction "2_2@3") (pintype "passive"))
    )
    (net (code "102") (name "Net-(U$10-3-Pad3@2)") (class "Default")
      (node (ref "U$10") (pin "3") (pinfunction "3_3") (pintype "passive"))
      (node (ref "U$10") (pin "3@2") (pinfunction "3_3@2") (pintype "passive"))
      (node (ref "U$10") (pin "3@3") (pinfunction "3_3@3") (pintype "passive"))
    )
    (net (code "103") (name "Net-(U$10-4-Pad4@2)") (class "Default")
      (node (ref "U$10") (pin "4") (pinfunction "4_4") (pintype "passive"))
      (node (ref "U$10") (pin "4@2") (pinfunction "4_4@2") (pintype "passive"))
      (node (ref "U$10") (pin "4@3") (pinfunction "4_4@3") (pintype "passive"))
    )
    (net (code "104") (name "Net-(U$10-5-Pad5@2)") (class "Default")
      (node (ref "U$10") (pin "5") (pinfunction "5_5") (pintype "passive"))
      (node (ref "U$10") (pin "5@2") (pinfunction "5_5@2") (pintype "passive"))
      (node (ref "U$10") (pin "5@3") (pinfunction "5_5@3") (pintype "passive"))
    )
    (net (code "105") (name "Net-(U$10-6-Pad6@2)") (class "Default")
      (node (ref "U$10") (pin "6") (pinfunction "6_6") (pintype "passive"))
      (node (ref "U$10") (pin "6@2") (pinfunction "6_6@2") (pintype "passive"))
      (node (ref "U$10") (pin "6@3") (pinfunction "6_6@3") (pintype "passive"))
    )
    (net (code "106") (name "Net-(U$10-7-Pad7@2)") (class "Default")
      (node (ref "U$10") (pin "7") (pinfunction "7_7") (pintype "passive"))
      (node (ref "U$10") (pin "7@2") (pinfunction "7_7@2") (pintype "passive"))
      (node (ref "U$10") (pin "7@3") (pinfunction "7_7@3") (pintype "passive"))
    )
    (net (code "107") (name "Net-(U$10-8-Pad8@2)") (class "Default")
      (node (ref "U$10") (pin "8") (pinfunction "8_8") (pintype "passive"))
      (node (ref "U$10") (pin "8@2") (pinfunction "8_8@2") (pintype "passive"))
      (node (ref "U$10") (pin "8@3") (pinfunction "8_8@3") (pintype "passive"))
    )
    (net (code "108") (name "Net-(U$10-9-Pad9@2)") (class "Default")
      (node (ref "U$10") (pin "9") (pinfunction "9_9") (pintype "passive"))
      (node (ref "U$10") (pin "9@2") (pinfunction "9_9@2") (pintype "passive"))
      (node (ref "U$10") (pin "9@3") (pinfunction "9_9@3") (pintype "passive"))
    )
    (net (code "109") (name "Net-(U$10-10-Pad10@2)") (class "Default")
      (node (ref "U$10") (pin "10") (pinfunction "10_10") (pintype "passive"))
      (node (ref "U$10") (pin "10@2") (pinfunction "10_10@2") (pintype "passive"))
      (node (ref "U$10") (pin "10@3") (pinfunction "10_10@3") (pintype "passive"))
    )
    (net (code "110") (name "Net-(U$10-11-Pad11@2)") (class "Default")
      (node (ref "U$10") (pin "11") (pinfunction "11_11") (pintype "passive"))
      (node (ref "U$10") (pin "11@2") (pinfunction "11_11@2") (pintype "passive"))
      (node (ref "U$10") (pin "11@3") (pinfunction "11_11@3") (pintype "passive"))
    )
    (net (code "111") (name "Net-(U$10-12-Pad12@2)") (class "Default")
      (node (ref "U$10") (pin "12") (pinfunction "12_12") (pintype "passive"))
      (node (ref "U$10") (pin "12@2") (pinfunction "12_12@2") (pintype "passive"))
      (node (ref "U$10") (pin "12@3") (pinfunction "12_12@3") (pintype "passive"))
    )
    (net (code "112") (name "Net-(U$10-13-Pad13@2)") (class "Default")
      (node (ref "U$10") (pin "13") (pinfunction "13_13") (pintype "passive"))
      (node (ref "U$10") (pin "13@2") (pinfunction "13_13@2") (pintype "passive"))
      (node (ref "U$10") (pin "13@3") (pinfunction "13_13@3") (pintype "passive"))
    )
    (net (code "113") (name "Net-(U$10-14-Pad14@2)") (class "Default")
      (node (ref "U$10") (pin "14") (pinfunction "14_14") (pintype "passive"))
      (node (ref "U$10") (pin "14@2") (pinfunction "14_14@2") (pintype "passive"))
      (node (ref "U$10") (pin "14@3") (pinfunction "14_14@3") (pintype "passive"))
    )
    (net (code "114") (name "Net-(U$10-15-Pad15@2)") (class "Default")
      (node (ref "U$10") (pin "15") (pinfunction "15_15") (pintype "passive"))
      (node (ref "U$10") (pin "15@2") (pinfunction "15_15@2") (pintype "passive"))
      (node (ref "U$10") (pin "15@3") (pinfunction "15_15@3") (pintype "passive"))
    )
    (net (code "115") (name "Net-(U$10-16-Pad16@2)") (class "Default")
      (node (ref "U$10") (pin "16") (pinfunction "16_16") (pintype "passive"))
      (node (ref "U$10") (pin "16@2") (pinfunction "16_16@2") (pintype "passive"))
      (node (ref "U$10") (pin "16@3") (pinfunction "16_16@3") (pintype "passive"))
    )
    (net (code "116") (name "Net-(U$11-1-Pad1@2)") (class "Default")
      (node (ref "U$11") (pin "1") (pinfunction "1_1") (pintype "passive"))
      (node (ref "U$11") (pin "1@2") (pinfunction "1_1@2") (pintype "passive"))
      (node (ref "U$11") (pin "1@3") (pinfunction "1_1@3") (pintype "passive"))
    )
    (net (code "117") (name "Net-(U$11-2-Pad2@2)") (class "Default")
      (node (ref "U$11") (pin "2") (pinfunction "2_2") (pintype "passive"))
      (node (ref "U$11") (pin "2@2") (pinfunction "2_2@2") (pintype "passive"))
      (node (ref "U$11") (pin "2@3") (pinfunction "2_2@3") (pintype "passive"))
    )
    (net (code "118") (name "Net-(U$11-3-Pad3@2)") (class "Default")
      (node (ref "U$11") (pin "3") (pinfunction "3_3") (pintype "passive"))
      (node (ref "U$11") (pin "3@2") (pinfunction "3_3@2") (pintype "passive"))
      (node (ref "U$11") (pin "3@3") (pinfunction "3_3@3") (pintype "passive"))
    )
    (net (code "119") (name "Net-(U$11-4-Pad4@2)") (class "Default")
      (node (ref "U$11") (pin "4") (pinfunction "4_4") (pintype "passive"))
      (node (ref "U$11") (pin "4@2") (pinfunction "4_4@2") (pintype "passive"))
      (node (ref "U$11") (pin "4@3") (pinfunction "4_4@3") (pintype "passive"))
    )
    (net (code "120") (name "Net-(U$11-5-Pad5@2)") (class "Default")
      (node (ref "U$11") (pin "5") (pinfunction "5_5") (pintype "passive"))
      (node (ref "U$11") (pin "5@2") (pinfunction "5_5@2") (pintype "passive"))
      (node (ref "U$11") (pin "5@3") (pinfunction "5_5@3") (pintype "passive"))
    )
    (net (code "121") (name "Net-(U$11-6-Pad6@2)") (class "Default")
      (node (ref "U$11") (pin "6") (pinfunction "6_6") (pintype "passive"))
      (node (ref "U$11") (pin "6@2") (pinfunction "6_6@2") (pintype "passive"))
      (node (ref "U$11") (pin "6@3") (pinfunction "6_6@3") (pintype "passive"))
    )
    (net (code "122") (name "Net-(U$11-7-Pad7@2)") (class "Default")
      (node (ref "U$11") (pin "7") (pinfunction "7_7") (pintype "passive"))
      (node (ref "U$11") (pin "7@2") (pinfunction "7_7@2") (pintype "passive"))
      (node (ref "U$11") (pin "7@3") (pinfunction "7_7@3") (pintype "passive"))
    )
    (net (code "123") (name "Net-(U$11-8-Pad8@2)") (class "Default")
      (node (ref "U$11") (pin "8") (pinfunction "8_8") (pintype "passive"))
      (node (ref "U$11") (pin "8@2") (pinfunction "8_8@2") (pintype "passive"))
      (node (ref "U$11") (pin "8@3") (pinfunction "8_8@3") (pintype "passive"))
    )
    (net (code "124") (name "Net-(U$11-9-Pad9@2)") (class "Default")
      (node (ref "U$11") (pin "9") (pinfunction "9_9") (pintype "passive"))
      (node (ref "U$11") (pin "9@2") (pinfunction "9_9@2") (pintype "passive"))
      (node (ref "U$11") (pin "9@3") (pinfunction "9_9@3") (pintype "passive"))
    )
    (net (code "125") (name "Net-(U$11-10-Pad10@2)") (class "Default")
      (node (ref "U$11") (pin "10") (pinfunction "10_10") (pintype "passive"))
      (node (ref "U$11") (pin "10@2") (pinfunction "10_10@2") (pintype "passive"))
      (node (ref "U$11") (pin "10@3") (pinfunction "10_10@3") (pintype "passive"))
    )
    (net (code "126") (name "Net-(U$11-11-Pad11@2)") (class "Default")
      (node (ref "U$11") (pin "11") (pinfunction "11_11") (pintype "passive"))
      (node (ref "U$11") (pin "11@2") (pinfunction "11_11@2") (pintype "passive"))
      (node (ref "U$11") (pin "11@3") (pinfunction "11_11@3") (pintype "passive"))
    )
    (net (code "127") (name "Net-(U$11-12-Pad12@2)") (class "Default")
      (node (ref "U$11") (pin "12") (pinfunction "12_12") (pintype "passive"))
      (node (ref "U$11") (pin "12@2") (pinfunction "12_12@2") (pintype "passive"))
      (node (ref "U$11") (pin "12@3") (pinfunction "12_12@3") (pintype "passive"))
    )
    (net (code "128") (name "Net-(U$11-13-Pad13@2)") (class "Default")
      (node (ref "U$11") (pin "13") (pinfunction "13_13") (pintype "passive"))
      (node (ref "U$11") (pin "13@2") (pinfunction "13_13@2") (pintype "passive"))
      (node (ref "U$11") (pin "13@3") (pinfunction "13_13@3") (pintype "passive"))
    )
    (net (code "129") (name "Net-(U$11-14-Pad14@2)") (class "Default")
      (node (ref "U$11") (pin "14") (pinfunction "14_14") (pintype "passive"))
      (node (ref "U$11") (pin "14@2") (pinfunction "14_14@2") (pintype "passive"))
      (node (ref "U$11") (pin "14@3") (pinfunction "14_14@3") (pintype "passive"))
    )
    (net (code "130") (name "Net-(U$11-15-Pad15@2)") (class "Default")
      (node (ref "U$11") (pin "15") (pinfunction "15_15") (pintype "passive"))
      (node (ref "U$11") (pin "15@2") (pinfunction "15_15@2") (pintype "passive"))
      (node (ref "U$11") (pin "15@3") (pinfunction "15_15@3") (pintype "passive"))
    )
    (net (code "131") (name "Net-(U$11-16-Pad16@2)") (class "Default")
      (node (ref "U$11") (pin "16") (pinfunction "16_16") (pintype "passive"))
      (node (ref "U$11") (pin "16@2") (pinfunction "16_16@2") (pintype "passive"))
      (node (ref "U$11") (pin "16@3") (pinfunction "16_16@3") (pintype "passive"))
    )
    (net (code "132") (name "Net-(U$12-1-Pad1@2)") (class "Default")
      (node (ref "U$12") (pin "1") (pinfunction "1_1") (pintype "passive"))
      (node (ref "U$12") (pin "1@2") (pinfunction "1_1@2") (pintype "passive"))
      (node (ref "U$12") (pin "1@3") (pinfunction "1_1@3") (pintype "passive"))
    )
    (net (code "133") (name "Net-(U$12-2-Pad2@2)") (class "Default")
      (node (ref "U$12") (pin "2") (pinfunction "2_2") (pintype "passive"))
      (node (ref "U$12") (pin "2@2") (pinfunction "2_2@2") (pintype "passive"))
      (node (ref "U$12") (pin "2@3") (pinfunction "2_2@3") (pintype "passive"))
    )
    (net (code "134") (name "Net-(U$12-3-Pad3@2)") (class "Default")
      (node (ref "U$12") (pin "3") (pinfunction "3_3") (pintype "passive"))
      (node (ref "U$12") (pin "3@2") (pinfunction "3_3@2") (pintype "passive"))
      (node (ref "U$12") (pin "3@3") (pinfunction "3_3@3") (pintype "passive"))
    )
    (net (code "135") (name "Net-(U$12-4-Pad4@2)") (class "Default")
      (node (ref "U$12") (pin "4") (pinfunction "4_4") (pintype "passive"))
      (node (ref "U$12") (pin "4@2") (pinfunction "4_4@2") (pintype "passive"))
      (node (ref "U$12") (pin "4@3") (pinfunction "4_4@3") (pintype "passive"))
    )
    (net (code "136") (name "Net-(U$12-5-Pad5@2)") (class "Default")
      (node (ref "U$12") (pin "5") (pinfunction "5_5") (pintype "passive"))
      (node (ref "U$12") (pin "5@2") (pinfunction "5_5@2") (pintype "passive"))
      (node (ref "U$12") (pin "5@3") (pinfunction "5_5@3") (pintype "passive"))
    )
    (net (code "137") (name "Net-(U$12-6-Pad6@2)") (class "Default")
      (node (ref "U$12") (pin "6") (pinfunction "6_6") (pintype "passive"))
      (node (ref "U$12") (pin "6@2") (pinfunction "6_6@2") (pintype "passive"))
      (node (ref "U$12") (pin "6@3") (pinfunction "6_6@3") (pintype "passive"))
    )
    (net (code "138") (name "Net-(U$12-7-Pad7@2)") (class "Default")
      (node (ref "U$12") (pin "7") (pinfunction "7_7") (pintype "passive"))
      (node (ref "U$12") (pin "7@2") (pinfunction "7_7@2") (pintype "passive"))
      (node (ref "U$12") (pin "7@3") (pinfunction "7_7@3") (pintype "passive"))
    )
    (net (code "139") (name "Net-(U$12-8-Pad8@2)") (class "Default")
      (node (ref "U$12") (pin "8") (pinfunction "8_8") (pintype "passive"))
      (node (ref "U$12") (pin "8@2") (pinfunction "8_8@2") (pintype "passive"))
      (node (ref "U$12") (pin "8@3") (pinfunction "8_8@3") (pintype "passive"))
    )
    (net (code "140") (name "Net-(U$12-9-Pad9@2)") (class "Default")
      (node (ref "U$12") (pin "9") (pinfunction "9_9") (pintype "passive"))
      (node (ref "U$12") (pin "9@2") (pinfunction "9_9@2") (pintype "passive"))
      (node (ref "U$12") (pin "9@3") (pinfunction "9_9@3") (pintype "passive"))
    )
    (net (code "141") (name "Net-(U$12-10-Pad10@2)") (class "Default")
      (node (ref "U$12") (pin "10") (pinfunction "10_10") (pintype "passive"))
      (node (ref "U$12") (pin "10@2") (pinfunction "10_10@2") (pintype "passive"))
      (node (ref "U$12") (pin "10@3") (pinfunction "10_10@3") (pintype "passive"))
    )
    (net (code "142") (name "Net-(U$12-11-Pad11@2)") (class "Default")
      (node (ref "U$12") (pin "11") (pinfunction "11_11") (pintype "passive"))
      (node (ref "U$12") (pin "11@2") (pinfunction "11_11@2") (pintype "passive"))
      (node (ref "U$12") (pin "11@3") (pinfunction "11_11@3") (pintype "passive"))
    )
    (net (code "143") (name "Net-(U$12-12-Pad12@2)") (class "Default")
      (node (ref "U$12") (pin "12") (pinfunction "12_12") (pintype "passive"))
      (node (ref "U$12") (pin "12@2") (pinfunction "12_12@2") (pintype "passive"))
      (node (ref "U$12") (pin "12@3") (pinfunction "12_12@3") (pintype "passive"))
    )
    (net (code "144") (name "Net-(U$12-13-Pad13@2)") (class "Default")
      (node (ref "U$12") (pin "13") (pinfunction "13_13") (pintype "passive"))
      (node (ref "U$12") (pin "13@2") (pinfunction "13_13@2") (pintype "passive"))
      (node (ref "U$12") (pin "13@3") (pinfunction "13_13@3") (pintype "passive"))
    )
    (net (code "145") (name "Net-(U$12-14-Pad14@2)") (class "Default")
      (node (ref "U$12") (pin "14") (pinfunction "14_14") (pintype "passive"))
      (node (ref "U$12") (pin "14@2") (pinfunction "14_14@2") (pintype "passive"))
      (node (ref "U$12") (pin "14@3") (pinfunction "14_14@3") (pintype "passive"))
    )
    (net (code "146") (name "Net-(U$12-15-Pad15@2)") (class "Default")
      (node (ref "U$12") (pin "15") (pinfunction "15_15") (pintype "passive"))
      (node (ref "U$12") (pin "15@2") (pinfunction "15_15@2") (pintype "passive"))
      (node (ref "U$12") (pin "15@3") (pinfunction "15_15@3") (pintype "passive"))
    )
    (net (code "147") (name "Net-(U$12-16-Pad16@2)") (class "Default")
      (node (ref "U$12") (pin "16") (pinfunction "16_16") (pintype "passive"))
      (node (ref "U$12") (pin "16@2") (pinfunction "16_16@2") (pintype "passive"))
      (node (ref "U$12") (pin "16@3") (pinfunction "16_16@3") (pintype "passive"))
    )
    (net (code "148") (name "Net-(U$13-1-Pad1@2)") (class "Default")
      (node (ref "U$13") (pin "1") (pinfunction "1_1") (pintype "passive"))
      (node (ref "U$13") (pin "1@2") (pinfunction "1_1@2") (pintype "passive"))
      (node (ref "U$13") (pin "1@3") (pinfunction "1_1@3") (pintype "passive"))
    )
    (net (code "149") (name "Net-(U$13-2-Pad2@2)") (class "Default")
      (node (ref "U$13") (pin "2") (pinfunction "2_2") (pintype "passive"))
      (node (ref "U$13") (pin "2@2") (pinfunction "2_2@2") (pintype "passive"))
      (node (ref "U$13") (pin "2@3") (pinfunction "2_2@3") (pintype "passive"))
    )
    (net (code "150") (name "Net-(U$13-3-Pad3@2)") (class "Default")
      (node (ref "U$13") (pin "3") (pinfunction "3_3") (pintype "passive"))
      (node (ref "U$13") (pin "3@2") (pinfunction "3_3@2") (pintype "passive"))
      (node (ref "U$13") (pin "3@3") (pinfunction "3_3@3") (pintype "passive"))
    )
    (net (code "151") (name "Net-(U$13-4-Pad4@2)") (class "Default")
      (node (ref "U$13") (pin "4") (pinfunction "4_4") (pintype "passive"))
      (node (ref "U$13") (pin "4@2") (pinfunction "4_4@2") (pintype "passive"))
      (node (ref "U$13") (pin "4@3") (pinfunction "4_4@3") (pintype "passive"))
    )
    (net (code "152") (name "Net-(U$13-5-Pad5@2)") (class "Default")
      (node (ref "U$13") (pin "5") (pinfunction "5_5") (pintype "passive"))
      (node (ref "U$13") (pin "5@2") (pinfunction "5_5@2") (pintype "passive"))
      (node (ref "U$13") (pin "5@3") (pinfunction "5_5@3") (pintype "passive"))
    )
    (net (code "153") (name "Net-(U$13-6-Pad6@2)") (class "Default")
      (node (ref "U$13") (pin "6") (pinfunction "6_6") (pintype "passive"))
      (node (ref "U$13") (pin "6@2") (pinfunction "6_6@2") (pintype "passive"))
      (node (ref "U$13") (pin "6@3") (pinfunction "6_6@3") (pintype "passive"))
    )
    (net (code "154") (name "Net-(U$13-7-Pad7@2)") (class "Default")
      (node (ref "U$13") (pin "7") (pinfunction "7_7") (pintype "passive"))
      (node (ref "U$13") (pin "7@2") (pinfunction "7_7@2") (pintype "passive"))
      (node (ref "U$13") (pin "7@3") (pinfunction "7_7@3") (pintype "passive"))
    )
    (net (code "155") (name "Net-(U$13-8-Pad8@2)") (class "Default")
      (node (ref "U$13") (pin "8") (pinfunction "8_8") (pintype "passive"))
      (node (ref "U$13") (pin "8@2") (pinfunction "8_8@2") (pintype "passive"))
      (node (ref "U$13") (pin "8@3") (pinfunction "8_8@3") (pintype "passive"))
    )
    (net (code "156") (name "Net-(U$13-9-Pad9@2)") (class "Default")
      (node (ref "U$13") (pin "9") (pinfunction "9_9") (pintype "passive"))
      (node (ref "U$13") (pin "9@2") (pinfunction "9_9@2") (pintype "passive"))
      (node (ref "U$13") (pin "9@3") (pinfunction "9_9@3") (pintype "passive"))
    )
    (net (code "157") (name "Net-(U$13-10-Pad10@2)") (class "Default")
      (node (ref "U$13") (pin "10") (pinfunction "10_10") (pintype "passive"))
      (node (ref "U$13") (pin "10@2") (pinfunction "10_10@2") (pintype "passive"))
      (node (ref "U$13") (pin "10@3") (pinfunction "10_10@3") (pintype "passive"))
    )
    (net (code "158") (name "Net-(U$13-11-Pad11@2)") (class "Default")
      (node (ref "U$13") (pin "11") (pinfunction "11_11") (pintype "passive"))
      (node (ref "U$13") (pin "11@2") (pinfunction "11_11@2") (pintype "passive"))
      (node (ref "U$13") (pin "11@3") (pinfunction "11_11@3") (pintype "passive"))
    )
    (net (code "159") (name "Net-(U$13-12-Pad12@2)") (class "Default")
      (node (ref "U$13") (pin "12") (pinfunction "12_12") (pintype "passive"))
      (node (ref "U$13") (pin "12@2") (pinfunction "12_12@2") (pintype "passive"))
      (node (ref "U$13") (pin "12@3") (pinfunction "12_12@3") (pintype "passive"))
    )
    (net (code "160") (name "Net-(U$13-13-Pad13@2)") (class "Default")
      (node (ref "U$13") (pin "13") (pinfunction "13_13") (pintype "passive"))
      (node (ref "U$13") (pin "13@2") (pinfunction "13_13@2") (pintype "passive"))
      (node (ref "U$13") (pin "13@3") (pinfunction "13_13@3") (pintype "passive"))
    )
    (net (code "161") (name "Net-(U$13-14-Pad14@2)") (class "Default")
      (node (ref "U$13") (pin "14") (pinfunction "14_14") (pintype "passive"))
      (node (ref "U$13") (pin "14@2") (pinfunction "14_14@2") (pintype "passive"))
      (node (ref "U$13") (pin "14@3") (pinfunction "14_14@3") (pintype "passive"))
    )
    (net (code "162") (name "Net-(U$13-15-Pad15@2)") (class "Default")
      (node (ref "U$13") (pin "15") (pinfunction "15_15") (pintype "passive"))
      (node (ref "U$13") (pin "15@2") (pinfunction "15_15@2") (pintype "passive"))
      (node (ref "U$13") (pin "15@3") (pinfunction "15_15@3") (pintype "passive"))
    )
    (net (code "163") (name "Net-(U$13-16-Pad16@2)") (class "Default")
      (node (ref "U$13") (pin "16") (pinfunction "16_16") (pintype "passive"))
      (node (ref "U$13") (pin "16@2") (pinfunction "16_16@2") (pintype "passive"))
      (node (ref "U$13") (pin "16@3") (pinfunction "16_16@3") (pintype "passive"))
    )
    (net (code "164") (name "Net-(U$14-1-Pad1@2)") (class "Default")
      (node (ref "U$14") (pin "1") (pinfunction "1_1") (pintype "passive"))
      (node (ref "U$14") (pin "1@2") (pinfunction "1_1@2") (pintype "passive"))
      (node (ref "U$14") (pin "1@3") (pinfunction "1_1@3") (pintype "passive"))
    )
    (net (code "165") (name "Net-(U$14-2-Pad2@2)") (class "Default")
      (node (ref "U$14") (pin "2") (pinfunction "2_2") (pintype "passive"))
      (node (ref "U$14") (pin "2@2") (pinfunction "2_2@2") (pintype "passive"))
      (node (ref "U$14") (pin "2@3") (pinfunction "2_2@3") (pintype "passive"))
    )
    (net (code "166") (name "Net-(U$14-3-Pad3@2)") (class "Default")
      (node (ref "U$14") (pin "3") (pinfunction "3_3") (pintype "passive"))
      (node (ref "U$14") (pin "3@2") (pinfunction "3_3@2") (pintype "passive"))
      (node (ref "U$14") (pin "3@3") (pinfunction "3_3@3") (pintype "passive"))
    )
    (net (code "167") (name "Net-(U$14-4-Pad4@2)") (class "Default")
      (node (ref "U$14") (pin "4") (pinfunction "4_4") (pintype "passive"))
      (node (ref "U$14") (pin "4@2") (pinfunction "4_4@2") (pintype "passive"))
      (node (ref "U$14") (pin "4@3") (pinfunction "4_4@3") (pintype "passive"))
    )
    (net (code "168") (name "Net-(U$14-5-Pad5@2)") (class "Default")
      (node (ref "U$14") (pin "5") (pinfunction "5_5") (pintype "passive"))
      (node (ref "U$14") (pin "5@2") (pinfunction "5_5@2") (pintype "passive"))
      (node (ref "U$14") (pin "5@3") (pinfunction "5_5@3") (pintype "passive"))
    )
    (net (code "169") (name "Net-(U$14-6-Pad6@2)") (class "Default")
      (node (ref "U$14") (pin "6") (pinfunction "6_6") (pintype "passive"))
      (node (ref "U$14") (pin "6@2") (pinfunction "6_6@2") (pintype "passive"))
      (node (ref "U$14") (pin "6@3") (pinfunction "6_6@3") (pintype "passive"))
    )
    (net (code "170") (name "Net-(U$14-7-Pad7@2)") (class "Default")
      (node (ref "U$14") (pin "7") (pinfunction "7_7") (pintype "passive"))
      (node (ref "U$14") (pin "7@2") (pinfunction "7_7@2") (pintype "passive"))
      (node (ref "U$14") (pin "7@3") (pinfunction "7_7@3") (pintype "passive"))
    )
    (net (code "171") (name "Net-(U$14-8-Pad8@2)") (class "Default")
      (node (ref "U$14") (pin "8") (pinfunction "8_8") (pintype "passive"))
      (node (ref "U$14") (pin "8@2") (pinfunction "8_8@2") (pintype "passive"))
      (node (ref "U$14") (pin "8@3") (pinfunction "8_8@3") (pintype "passive"))
    )
    (net (code "172") (name "Net-(U$14-9-Pad9@2)") (class "Default")
      (node (ref "U$14") (pin "9") (pinfunction "9_9") (pintype "passive"))
      (node (ref "U$14") (pin "9@2") (pinfunction "9_9@2") (pintype "passive"))
      (node (ref "U$14") (pin "9@3") (pinfunction "9_9@3") (pintype "passive"))
    )
    (net (code "173") (name "Net-(U$14-10-Pad10@2)") (class "Default")
      (node (ref "U$14") (pin "10") (pinfunction "10_10") (pintype "passive"))
      (node (ref "U$14") (pin "10@2") (pinfunction "10_10@2") (pintype "passive"))
      (node (ref "U$14") (pin "10@3") (pinfunction "10_10@3") (pintype "passive"))
    )
    (net (code "174") (name "Net-(U$14-11-Pad11@2)") (class "Default")
      (node (ref "U$14") (pin "11") (pinfunction "11_11") (pintype "passive"))
      (node (ref "U$14") (pin "11@2") (pinfunction "11_11@2") (pintype "passive"))
      (node (ref "U$14") (pin "11@3") (pinfunction "11_11@3") (pintype "passive"))
    )
    (net (code "175") (name "Net-(U$14-12-Pad12@2)") (class "Default")
      (node (ref "U$14") (pin "12") (pinfunction "12_12") (pintype "passive"))
      (node (ref "U$14") (pin "12@2") (pinfunction "12_12@2") (pintype "passive"))
      (node (ref "U$14") (pin "12@3") (pinfunction "12_12@3") (pintype "passive"))
    )
    (net (code "176") (name "Net-(U$14-13-Pad13@2)") (class "Default")
      (node (ref "U$14") (pin "13") (pinfunction "13_13") (pintype "passive"))
      (node (ref "U$14") (pin "13@2") (pinfunction "13_13@2") (pintype "passive"))
      (node (ref "U$14") (pin "13@3") (pinfunction "13_13@3") (pintype "passive"))
    )
    (net (code "177") (name "Net-(U$14-14-Pad14@2)") (class "Default")
      (node (ref "U$14") (pin "14") (pinfunction "14_14") (pintype "passive"))
      (node (ref "U$14") (pin "14@2") (pinfunction "14_14@2") (pintype "passive"))
      (node (ref "U$14") (pin "14@3") (pinfunction "14_14@3") (pintype "passive"))
    )
    (net (code "178") (name "Net-(U$14-15-Pad15@2)") (class "Default")
      (node (ref "U$14") (pin "15") (pinfunction "15_15") (pintype "passive"))
      (node (ref "U$14") (pin "15@2") (pinfunction "15_15@2") (pintype "passive"))
      (node (ref "U$14") (pin "15@3") (pinfunction "15_15@3") (pintype "passive"))
    )
    (net (code "179") (name "Net-(U$14-16-Pad16@2)") (class "Default")
      (node (ref "U$14") (pin "16") (pinfunction "16_16") (pintype "passive"))
      (node (ref "U$14") (pin "16@2") (pinfunction "16_16@2") (pintype "passive"))
      (node (ref "U$14") (pin "16@3") (pinfunction "16_16@3") (pintype "passive"))
    )
    (net (code "180") (name "Net-(U$15-1-Pad1@2)") (class "Default")
      (node (ref "U$15") (pin "1") (pinfunction "1_1") (pintype "passive"))
      (node (ref "U$15") (pin "1@2") (pinfunction "1_1@2") (pintype "passive"))
      (node (ref "U$15") (pin "1@3") (pinfunction "1_1@3") (pintype "passive"))
    )
    (net (code "181") (name "Net-(U$15-2-Pad2@2)") (class "Default")
      (node (ref "U$15") (pin "2") (pinfunction "2_2") (pintype "passive"))
      (node (ref "U$15") (pin "2@2") (pinfunction "2_2@2") (pintype "passive"))
      (node (ref "U$15") (pin "2@3") (pinfunction "2_2@3") (pintype "passive"))
    )
    (net (code "182") (name "Net-(U$15-3-Pad3@2)") (class "Default")
      (node (ref "U$15") (pin "3") (pinfunction "3_3") (pintype "passive"))
      (node (ref "U$15") (pin "3@2") (pinfunction "3_3@2") (pintype "passive"))
      (node (ref "U$15") (pin "3@3") (pinfunction "3_3@3") (pintype "passive"))
    )
    (net (code "183") (name "Net-(U$15-4-Pad4@2)") (class "Default")
      (node (ref "U$15") (pin "4") (pinfunction "4_4") (pintype "passive"))
      (node (ref "U$15") (pin "4@2") (pinfunction "4_4@2") (pintype "passive"))
      (node (ref "U$15") (pin "4@3") (pinfunction "4_4@3") (pintype "passive"))
    )
    (net (code "184") (name "Net-(U$15-5-Pad5@2)") (class "Default")
      (node (ref "U$15") (pin "5") (pinfunction "5_5") (pintype "passive"))
      (node (ref "U$15") (pin "5@2") (pinfunction "5_5@2") (pintype "passive"))
      (node (ref "U$15") (pin "5@3") (pinfunction "5_5@3") (pintype "passive"))
    )
    (net (code "185") (name "Net-(U$15-6-Pad6@2)") (class "Default")
      (node (ref "U$15") (pin "6") (pinfunction "6_6") (pintype "passive"))
      (node (ref "U$15") (pin "6@2") (pinfunction "6_6@2") (pintype "passive"))
      (node (ref "U$15") (pin "6@3") (pinfunction "6_6@3") (pintype "passive"))
    )
    (net (code "186") (name "Net-(U$15-7-Pad7@2)") (class "Default")
      (node (ref "U$15") (pin "7") (pinfunction "7_7") (pintype "passive"))
      (node (ref "U$15") (pin "7@2") (pinfunction "7_7@2") (pintype "passive"))
      (node (ref "U$15") (pin "7@3") (pinfunction "7_7@3") (pintype "passive"))
    )
    (net (code "187") (name "Net-(U$15-8-Pad8@2)") (class "Default")
      (node (ref "U$15") (pin "8") (pinfunction "8_8") (pintype "passive"))
      (node (ref "U$15") (pin "8@2") (pinfunction "8_8@2") (pintype "passive"))
      (node (ref "U$15") (pin "8@3") (pinfunction "8_8@3") (pintype "passive"))
    )
    (net (code "188") (name "Net-(U$15-9-Pad9@2)") (class "Default")
      (node (ref "U$15") (pin "9") (pinfunction "9_9") (pintype "passive"))
      (node (ref "U$15") (pin "9@2") (pinfunction "9_9@2") (pintype "passive"))
      (node (ref "U$15") (pin "9@3") (pinfunction "9_9@3") (pintype "passive"))
    )
    (net (code "189") (name "Net-(U$15-10-Pad10@2)") (class "Default")
      (node (ref "U$15") (pin "10") (pinfunction "10_10") (pintype "passive"))
      (node (ref "U$15") (pin "10@2") (pinfunction "10_10@2") (pintype "passive"))
      (node (ref "U$15") (pin "10@3") (pinfunction "10_10@3") (pintype "passive"))
    )
    (net (code "190") (name "Net-(U$15-11-Pad11@2)") (class "Default")
      (node (ref "U$15") (pin "11") (pinfunction "11_11") (pintype "passive"))
      (node (ref "U$15") (pin "11@2") (pinfunction "11_11@2") (pintype "passive"))
      (node (ref "U$15") (pin "11@3") (pinfunction "11_11@3") (pintype "passive"))
    )
    (net (code "191") (name "Net-(U$15-12-Pad12@2)") (class "Default")
      (node (ref "U$15") (pin "12") (pinfunction "12_12") (pintype "passive"))
      (node (ref "U$15") (pin "12@2") (pinfunction "12_12@2") (pintype "passive"))
      (node (ref "U$15") (pin "12@3") (pinfunction "12_12@3") (pintype "passive"))
    )
    (net (code "192") (name "Net-(U$15-13-Pad13@2)") (class "Default")
      (node (ref "U$15") (pin "13") (pinfunction "13_13") (pintype "passive"))
      (node (ref "U$15") (pin "13@2") (pinfunction "13_13@2") (pintype "passive"))
      (node (ref "U$15") (pin "13@3") (pinfunction "13_13@3") (pintype "passive"))
    )
    (net (code "193") (name "Net-(U$15-14-Pad14@2)") (class "Default")
      (node (ref "U$15") (pin "14") (pinfunction "14_14") (pintype "passive"))
      (node (ref "U$15") (pin "14@2") (pinfunction "14_14@2") (pintype "passive"))
      (node (ref "U$15") (pin "14@3") (pinfunction "14_14@3") (pintype "passive"))
    )
    (net (code "194") (name "Net-(U$15-15-Pad15@2)") (class "Default")
      (node (ref "U$15") (pin "15") (pinfunction "15_15") (pintype "passive"))
      (node (ref "U$15") (pin "15@2") (pinfunction "15_15@2") (pintype "passive"))
      (node (ref "U$15") (pin "15@3") (pinfunction "15_15@3") (pintype "passive"))
    )
    (net (code "195") (name "Net-(U$15-16-Pad16@2)") (class "Default")
      (node (ref "U$15") (pin "16") (pinfunction "16_16") (pintype "passive"))
      (node (ref "U$15") (pin "16@2") (pinfunction "16_16@2") (pintype "passive"))
      (node (ref "U$15") (pin "16@3") (pinfunction "16_16@3") (pintype "passive"))
    )
    (net (code "196") (name "Net-(U$16-1-Pad1@2)") (class "Default")
      (node (ref "U$16") (pin "1") (pinfunction "1_1") (pintype "passive"))
      (node (ref "U$16") (pin "1@2") (pinfunction "1_1@2") (pintype "passive"))
      (node (ref "U$16") (pin "1@3") (pinfunction "1_1@3") (pintype "passive"))
    )
    (net (code "197") (name "Net-(U$16-2-Pad2@2)") (class "Default")
      (node (ref "U$16") (pin "2") (pinfunction "2_2") (pintype "passive"))
      (node (ref "U$16") (pin "2@2") (pinfunction "2_2@2") (pintype "passive"))
      (node (ref "U$16") (pin "2@3") (pinfunction "2_2@3") (pintype "passive"))
    )
    (net (code "198") (name "Net-(U$16-3-Pad3@2)") (class "Default")
      (node (ref "U$16") (pin "3") (pinfunction "3_3") (pintype "passive"))
      (node (ref "U$16") (pin "3@2") (pinfunction "3_3@2") (pintype "passive"))
      (node (ref "U$16") (pin "3@3") (pinfunction "3_3@3") (pintype "passive"))
    )
    (net (code "199") (name "Net-(U$16-4-Pad4@2)") (class "Default")
      (node (ref "U$16") (pin "4") (pinfunction "4_4") (pintype "passive"))
      (node (ref "U$16") (pin "4@2") (pinfunction "4_4@2") (pintype "passive"))
      (node (ref "U$16") (pin "4@3") (pinfunction "4_4@3") (pintype "passive"))
    )
    (net (code "200") (name "Net-(U$16-5-Pad5@2)") (class "Default")
      (node (ref "U$16") (pin "5") (pinfunction "5_5") (pintype "passive"))
      (node (ref "U$16") (pin "5@2") (pinfunction "5_5@2") (pintype "passive"))
      (node (ref "U$16") (pin "5@3") (pinfunction "5_5@3") (pintype "passive"))
    )
    (net (code "201") (name "Net-(U$16-6-Pad6@2)") (class "Default")
      (node (ref "U$16") (pin "6") (pinfunction "6_6") (pintype "passive"))
      (node (ref "U$16") (pin "6@2") (pinfunction "6_6@2") (pintype "passive"))
      (node (ref "U$16") (pin "6@3") (pinfunction "6_6@3") (pintype "passive"))
    )
    (net (code "202") (name "Net-(U$16-7-Pad7@2)") (class "Default")
      (node (ref "U$16") (pin "7") (pinfunction "7_7") (pintype "passive"))
      (node (ref "U$16") (pin "7@2") (pinfunction "7_7@2") (pintype "passive"))
      (node (ref "U$16") (pin "7@3") (pinfunction "7_7@3") (pintype "passive"))
    )
    (net (code "203") (name "Net-(U$16-8-Pad8@2)") (class "Default")
      (node (ref "U$16") (pin "8") (pinfunction "8_8") (pintype "passive"))
      (node (ref "U$16") (pin "8@2") (pinfunction "8_8@2") (pintype "passive"))
      (node (ref "U$16") (pin "8@3") (pinfunction "8_8@3") (pintype "passive"))
    )
    (net (code "204") (name "Net-(U$16-9-Pad9@2)") (class "Default")
      (node (ref "U$16") (pin "9") (pinfunction "9_9") (pintype "passive"))
      (node (ref "U$16") (pin "9@2") (pinfunction "9_9@2") (pintype "passive"))
      (node (ref "U$16") (pin "9@3") (pinfunction "9_9@3") (pintype "passive"))
    )
    (net (code "205") (name "Net-(U$16-10-Pad10@2)") (class "Default")
      (node (ref "U$16") (pin "10") (pinfunction "10_10") (pintype "passive"))
      (node (ref "U$16") (pin "10@2") (pinfunction "10_10@2") (pintype "passive"))
      (node (ref "U$16") (pin "10@3") (pinfunction "10_10@3") (pintype "passive"))
    )
    (net (code "206") (name "Net-(U$16-11-Pad11@2)") (class "Default")
      (node (ref "U$16") (pin "11") (pinfunction "11_11") (pintype "passive"))
      (node (ref "U$16") (pin "11@2") (pinfunction "11_11@2") (pintype "passive"))
      (node (ref "U$16") (pin "11@3") (pinfunction "11_11@3") (pintype "passive"))
    )
    (net (code "207") (name "Net-(U$16-12-Pad12@2)") (class "Default")
      (node (ref "U$16") (pin "12") (pinfunction "12_12") (pintype "passive"))
      (node (ref "U$16") (pin "12@2") (pinfunction "12_12@2") (pintype "passive"))
      (node (ref "U$16") (pin "12@3") (pinfunction "12_12@3") (pintype "passive"))
    )
    (net (code "208") (name "Net-(U$16-13-Pad13@2)") (class "Default")
      (node (ref "U$16") (pin "13") (pinfunction "13_13") (pintype "passive"))
      (node (ref "U$16") (pin "13@2") (pinfunction "13_13@2") (pintype "passive"))
      (node (ref "U$16") (pin "13@3") (pinfunction "13_13@3") (pintype "passive"))
    )
    (net (code "209") (name "Net-(U$16-14-Pad14@2)") (class "Default")
      (node (ref "U$16") (pin "14") (pinfunction "14_14") (pintype "passive"))
      (node (ref "U$16") (pin "14@2") (pinfunction "14_14@2") (pintype "passive"))
      (node (ref "U$16") (pin "14@3") (pinfunction "14_14@3") (pintype "passive"))
    )
    (net (code "210") (name "Net-(U$16-15-Pad15@2)") (class "Default")
      (node (ref "U$16") (pin "15") (pinfunction "15_15") (pintype "passive"))
      (node (ref "U$16") (pin "15@2") (pinfunction "15_15@2") (pintype "passive"))
      (node (ref "U$16") (pin "15@3") (pinfunction "15_15@3") (pintype "passive"))
    )
    (net (code "211") (name "Net-(U$16-16-Pad16@2)") (class "Default")
      (node (ref "U$16") (pin "16") (pinfunction "16_16") (pintype "passive"))
      (node (ref "U$16") (pin "16@2") (pinfunction "16_16@2") (pintype "passive"))
      (node (ref "U$16") (pin "16@3") (pinfunction "16_16@3") (pintype "passive"))
    )
    (net (code "212") (name "Net-(U$17-1-Pad1@2)") (class "Default")
      (node (ref "U$17") (pin "1") (pinfunction "1_1") (pintype "passive"))
      (node (ref "U$17") (pin "1@2") (pinfunction "1_1@2") (pintype "passive"))
      (node (ref "U$17") (pin "1@3") (pinfunction "1_1@3") (pintype "passive"))
    )
    (net (code "213") (name "Net-(U$17-2-Pad2@2)") (class "Default")
      (node (ref "U$17") (pin "2") (pinfunction "2_2") (pintype "passive"))
      (node (ref "U$17") (pin "2@2") (pinfunction "2_2@2") (pintype "passive"))
      (node (ref "U$17") (pin "2@3") (pinfunction "2_2@3") (pintype "passive"))
    )
    (net (code "214") (name "Net-(U$17-3-Pad3@2)") (class "Default")
      (node (ref "U$17") (pin "3") (pinfunction "3_3") (pintype "passive"))
      (node (ref "U$17") (pin "3@2") (pinfunction "3_3@2") (pintype "passive"))
      (node (ref "U$17") (pin "3@3") (pinfunction "3_3@3") (pintype "passive"))
    )
    (net (code "215") (name "Net-(U$17-4-Pad4@2)") (class "Default")
      (node (ref "U$17") (pin "4") (pinfunction "4_4") (pintype "passive"))
      (node (ref "U$17") (pin "4@2") (pinfunction "4_4@2") (pintype "passive"))
      (node (ref "U$17") (pin "4@3") (pinfunction "4_4@3") (pintype "passive"))
    )
    (net (code "216") (name "Net-(U$17-5-Pad5@2)") (class "Default")
      (node (ref "U$17") (pin "5") (pinfunction "5_5") (pintype "passive"))
      (node (ref "U$17") (pin "5@2") (pinfunction "5_5@2") (pintype "passive"))
      (node (ref "U$17") (pin "5@3") (pinfunction "5_5@3") (pintype "passive"))
    )
    (net (code "217") (name "Net-(U$17-6-Pad6@2)") (class "Default")
      (node (ref "U$17") (pin "6") (pinfunction "6_6") (pintype "passive"))
      (node (ref "U$17") (pin "6@2") (pinfunction "6_6@2") (pintype "passive"))
      (node (ref "U$17") (pin "6@3") (pinfunction "6_6@3") (pintype "passive"))
    )
    (net (code "218") (name "Net-(U$17-7-Pad7@2)") (class "Default")
      (node (ref "U$17") (pin "7") (pinfunction "7_7") (pintype "passive"))
      (node (ref "U$17") (pin "7@2") (pinfunction "7_7@2") (pintype "passive"))
      (node (ref "U$17") (pin "7@3") (pinfunction "7_7@3") (pintype "passive"))
    )
    (net (code "219") (name "Net-(U$17-8-Pad8@2)") (class "Default")
      (node (ref "U$17") (pin "8") (pinfunction "8_8") (pintype "passive"))
      (node (ref "U$17") (pin "8@2") (pinfunction "8_8@2") (pintype "passive"))
      (node (ref "U$17") (pin "8@3") (pinfunction "8_8@3") (pintype "passive"))
    )
    (net (code "220") (name "Net-(U$17-9-Pad9@2)") (class "Default")
      (node (ref "U$17") (pin "9") (pinfunction "9_9") (pintype "passive"))
      (node (ref "U$17") (pin "9@2") (pinfunction "9_9@2") (pintype "passive"))
      (node (ref "U$17") (pin "9@3") (pinfunction "9_9@3") (pintype "passive"))
    )
    (net (code "221") (name "Net-(U$17-10-Pad10@2)") (class "Default")
      (node (ref "U$17") (pin "10") (pinfunction "10_10") (pintype "passive"))
      (node (ref "U$17") (pin "10@2") (pinfunction "10_10@2") (pintype "passive"))
      (node (ref "U$17") (pin "10@3") (pinfunction "10_10@3") (pintype "passive"))
    )
    (net (code "222") (name "Net-(U$17-11-Pad11@2)") (class "Default")
      (node (ref "U$17") (pin "11") (pinfunction "11_11") (pintype "passive"))
      (node (ref "U$17") (pin "11@2") (pinfunction "11_11@2") (pintype "passive"))
      (node (ref "U$17") (pin "11@3") (pinfunction "11_11@3") (pintype "passive"))
    )
    (net (code "223") (name "Net-(U$17-12-Pad12@2)") (class "Default")
      (node (ref "U$17") (pin "12") (pinfunction "12_12") (pintype "passive"))
      (node (ref "U$17") (pin "12@2") (pinfunction "12_12@2") (pintype "passive"))
      (node (ref "U$17") (pin "12@3") (pinfunction "12_12@3") (pintype "passive"))
    )
    (net (code "224") (name "Net-(U$17-13-Pad13@2)") (class "Default")
      (node (ref "U$17") (pin "13") (pinfunction "13_13") (pintype "passive"))
      (node (ref "U$17") (pin "13@2") (pinfunction "13_13@2") (pintype "passive"))
      (node (ref "U$17") (pin "13@3") (pinfunction "13_13@3") (pintype "passive"))
    )
    (net (code "225") (name "Net-(U$17-14-Pad14@2)") (class "Default")
      (node (ref "U$17") (pin "14") (pinfunction "14_14") (pintype "passive"))
      (node (ref "U$17") (pin "14@2") (pinfunction "14_14@2") (pintype "passive"))
      (node (ref "U$17") (pin "14@3") (pinfunction "14_14@3") (pintype "passive"))
    )
    (net (code "226") (name "Net-(U$17-15-Pad15@2)") (class "Default")
      (node (ref "U$17") (pin "15") (pinfunction "15_15") (pintype "passive"))
      (node (ref "U$17") (pin "15@2") (pinfunction "15_15@2") (pintype "passive"))
      (node (ref "U$17") (pin "15@3") (pinfunction "15_15@3") (pintype "passive"))
    )
    (net (code "227") (name "Net-(U$17-16-Pad16@2)") (class "Default")
      (node (ref "U$17") (pin "16") (pinfunction "16_16") (pintype "passive"))
      (node (ref "U$17") (pin "16@2") (pinfunction "16_16@2") (pintype "passive"))
      (node (ref "U$17") (pin "16@3") (pinfunction "16_16@3") (pintype "passive"))
    )
    (net (code "228") (name "Net-(U$18-1-Pad1@2)") (class "Default")
      (node (ref "U$18") (pin "1") (pinfunction "1_1") (pintype "passive"))
      (node (ref "U$18") (pin "1@2") (pinfunction "1_1@2") (pintype "passive"))
      (node (ref "U$18") (pin "1@3") (pinfunction "1_1@3") (pintype "passive"))
    )
    (net (code "229") (name "Net-(U$18-2-Pad2@2)") (class "Default")
      (node (ref "U$18") (pin "2") (pinfunction "2_2") (pintype "passive"))
      (node (ref "U$18") (pin "2@2") (pinfunction "2_2@2") (pintype "passive"))
      (node (ref "U$18") (pin "2@3") (pinfunction "2_2@3") (pintype "passive"))
    )
    (net (code "230") (name "Net-(U$18-3-Pad3@2)") (class "Default")
      (node (ref "U$18") (pin "3") (pinfunction "3_3") (pintype "passive"))
      (node (ref "U$18") (pin "3@2") (pinfunction "3_3@2") (pintype "passive"))
      (node (ref "U$18") (pin "3@3") (pinfunction "3_3@3") (pintype "passive"))
    )
    (net (code "231") (name "Net-(U$18-4-Pad4@2)") (class "Default")
      (node (ref "U$18") (pin "4") (pinfunction "4_4") (pintype "passive"))
      (node (ref "U$18") (pin "4@2") (pinfunction "4_4@2") (pintype "passive"))
      (node (ref "U$18") (pin "4@3") (pinfunction "4_4@3") (pintype "passive"))
    )
    (net (code "232") (name "Net-(U$18-5-Pad5@2)") (class "Default")
      (node (ref "U$18") (pin "5") (pinfunction "5_5") (pintype "passive"))
      (node (ref "U$18") (pin "5@2") (pinfunction "5_5@2") (pintype "passive"))
      (node (ref "U$18") (pin "5@3") (pinfunction "5_5@3") (pintype "passive"))
    )
    (net (code "233") (name "Net-(U$18-6-Pad6@2)") (class "Default")
      (node (ref "U$18") (pin "6") (pinfunction "6_6") (pintype "passive"))
      (node (ref "U$18") (pin "6@2") (pinfunction "6_6@2") (pintype "passive"))
      (node (ref "U$18") (pin "6@3") (pinfunction "6_6@3") (pintype "passive"))
    )
    (net (code "234") (name "Net-(U$18-7-Pad7@2)") (class "Default")
      (node (ref "U$18") (pin "7") (pinfunction "7_7") (pintype "passive"))
      (node (ref "U$18") (pin "7@2") (pinfunction "7_7@2") (pintype "passive"))
      (node (ref "U$18") (pin "7@3") (pinfunction "7_7@3") (pintype "passive"))
    )
    (net (code "235") (name "Net-(U$18-8-Pad8@2)") (class "Default")
      (node (ref "U$18") (pin "8") (pinfunction "8_8") (pintype "passive"))
      (node (ref "U$18") (pin "8@2") (pinfunction "8_8@2") (pintype "passive"))
      (node (ref "U$18") (pin "8@3") (pinfunction "8_8@3") (pintype "passive"))
    )
    (net (code "236") (name "Net-(U$18-9-Pad9@2)") (class "Default")
      (node (ref "U$18") (pin "9") (pinfunction "9_9") (pintype "passive"))
      (node (ref "U$18") (pin "9@2") (pinfunction "9_9@2") (pintype "passive"))
      (node (ref "U$18") (pin "9@3") (pinfunction "9_9@3") (pintype "passive"))
    )
    (net (code "237") (name "Net-(U$18-10-Pad10@2)") (class "Default")
      (node (ref "U$18") (pin "10") (pinfunction "10_10") (pintype "passive"))
      (node (ref "U$18") (pin "10@2") (pinfunction "10_10@2") (pintype "passive"))
      (node (ref "U$18") (pin "10@3") (pinfunction "10_10@3") (pintype "passive"))
    )
    (net (code "238") (name "Net-(U$18-11-Pad11@2)") (class "Default")
      (node (ref "U$18") (pin "11") (pinfunction "11_11") (pintype "passive"))
      (node (ref "U$18") (pin "11@2") (pinfunction "11_11@2") (pintype "passive"))
      (node (ref "U$18") (pin "11@3") (pinfunction "11_11@3") (pintype "passive"))
    )
    (net (code "239") (name "Net-(U$18-12-Pad12@2)") (class "Default")
      (node (ref "U$18") (pin "12") (pinfunction "12_12") (pintype "passive"))
      (node (ref "U$18") (pin "12@2") (pinfunction "12_12@2") (pintype "passive"))
      (node (ref "U$18") (pin "12@3") (pinfunction "12_12@3") (pintype "passive"))
    )
    (net (code "240") (name "Net-(U$18-13-Pad13@2)") (class "Default")
      (node (ref "U$18") (pin "13") (pinfunction "13_13") (pintype "passive"))
      (node (ref "U$18") (pin "13@2") (pinfunction "13_13@2") (pintype "passive"))
      (node (ref "U$18") (pin "13@3") (pinfunction "13_13@3") (pintype "passive"))
    )
    (net (code "241") (name "Net-(U$18-14-Pad14@2)") (class "Default")
      (node (ref "U$18") (pin "14") (pinfunction "14_14") (pintype "passive"))
      (node (ref "U$18") (pin "14@2") (pinfunction "14_14@2") (pintype "passive"))
      (node (ref "U$18") (pin "14@3") (pinfunction "14_14@3") (pintype "passive"))
    )
    (net (code "242") (name "Net-(U$18-15-Pad15@2)") (class "Default")
      (node (ref "U$18") (pin "15") (pinfunction "15_15") (pintype "passive"))
      (node (ref "U$18") (pin "15@2") (pinfunction "15_15@2") (pintype "passive"))
      (node (ref "U$18") (pin "15@3") (pinfunction "15_15@3") (pintype "passive"))
    )
    (net (code "243") (name "Net-(U$18-16-Pad16@2)") (class "Default")
      (node (ref "U$18") (pin "16") (pinfunction "16_16") (pintype "passive"))
      (node (ref "U$18") (pin "16@2") (pinfunction "16_16@2") (pintype "passive"))
      (node (ref "U$18") (pin "16@3") (pinfunction "16_16@3") (pintype "passive"))
    )
    (net (code "244") (name "Net-(U$19-1-Pad1@2)") (class "Default")
      (node (ref "U$19") (pin "1") (pinfunction "1_1") (pintype "passive"))
      (node (ref "U$19") (pin "1@2") (pinfunction "1_1@2") (pintype "passive"))
      (node (ref "U$19") (pin "1@3") (pinfunction "1_1@3") (pintype "passive"))
    )
    (net (code "245") (name "Net-(U$19-2-Pad2@2)") (class "Default")
      (node (ref "U$19") (pin "2") (pinfunction "2_2") (pintype "passive"))
      (node (ref "U$19") (pin "2@2") (pinfunction "2_2@2") (pintype "passive"))
      (node (ref "U$19") (pin "2@3") (pinfunction "2_2@3") (pintype "passive"))
    )
    (net (code "246") (name "Net-(U$19-3-Pad3@2)") (class "Default")
      (node (ref "U$19") (pin "3") (pinfunction "3_3") (pintype "passive"))
      (node (ref "U$19") (pin "3@2") (pinfunction "3_3@2") (pintype "passive"))
      (node (ref "U$19") (pin "3@3") (pinfunction "3_3@3") (pintype "passive"))
    )
    (net (code "247") (name "Net-(U$19-4-Pad4@2)") (class "Default")
      (node (ref "U$19") (pin "4") (pinfunction "4_4") (pintype "passive"))
      (node (ref "U$19") (pin "4@2") (pinfunction "4_4@2") (pintype "passive"))
      (node (ref "U$19") (pin "4@3") (pinfunction "4_4@3") (pintype "passive"))
    )
    (net (code "248") (name "Net-(U$19-5-Pad5@2)") (class "Default")
      (node (ref "U$19") (pin "5") (pinfunction "5_5") (pintype "passive"))
      (node (ref "U$19") (pin "5@2") (pinfunction "5_5@2") (pintype "passive"))
      (node (ref "U$19") (pin "5@3") (pinfunction "5_5@3") (pintype "passive"))
    )
    (net (code "249") (name "Net-(U$19-6-Pad6@2)") (class "Default")
      (node (ref "U$19") (pin "6") (pinfunction "6_6") (pintype "passive"))
      (node (ref "U$19") (pin "6@2") (pinfunction "6_6@2") (pintype "passive"))
      (node (ref "U$19") (pin "6@3") (pinfunction "6_6@3") (pintype "passive"))
    )
    (net (code "250") (name "Net-(U$19-7-Pad7@2)") (class "Default")
      (node (ref "U$19") (pin "7") (pinfunction "7_7") (pintype "passive"))
      (node (ref "U$19") (pin "7@2") (pinfunction "7_7@2") (pintype "passive"))
      (node (ref "U$19") (pin "7@3") (pinfunction "7_7@3") (pintype "passive"))
    )
    (net (code "251") (name "Net-(U$19-8-Pad8@2)") (class "Default")
      (node (ref "U$19") (pin "8") (pinfunction "8_8") (pintype "passive"))
      (node (ref "U$19") (pin "8@2") (pinfunction "8_8@2") (pintype "passive"))
      (node (ref "U$19") (pin "8@3") (pinfunction "8_8@3") (pintype "passive"))
    )
    (net (code "252") (name "Net-(U$19-9-Pad9@2)") (class "Default")
      (node (ref "U$19") (pin "9") (pinfunction "9_9") (pintype "passive"))
      (node (ref "U$19") (pin "9@2") (pinfunction "9_9@2") (pintype "passive"))
      (node (ref "U$19") (pin "9@3") (pinfunction "9_9@3") (pintype "passive"))
    )
    (net (code "253") (name "Net-(U$19-10-Pad10@2)") (class "Default")
      (node (ref "U$19") (pin "10") (pinfunction "10_10") (pintype "passive"))
      (node (ref "U$19") (pin "10@2") (pinfunction "10_10@2") (pintype "passive"))
      (node (ref "U$19") (pin "10@3") (pinfunction "10_10@3") (pintype "passive"))
    )
    (net (code "254") (name "Net-(U$19-11-Pad11@2)") (class "Default")
      (node (ref "U$19") (pin "11") (pinfunction "11_11") (pintype "passive"))
      (node (ref "U$19") (pin "11@2") (pinfunction "11_11@2") (pintype "passive"))
      (node (ref "U$19") (pin "11@3") (pinfunction "11_11@3") (pintype "passive"))
    )
    (net (code "255") (name "Net-(U$19-12-Pad12@2)") (class "Default")
      (node (ref "U$19") (pin "12") (pinfunction "12_12") (pintype "passive"))
      (node (ref "U$19") (pin "12@2") (pinfunction "12_12@2") (pintype "passive"))
      (node (ref "U$19") (pin "12@3") (pinfunction "12_12@3") (pintype "passive"))
    )
    (net (code "256") (name "Net-(U$19-13-Pad13@2)") (class "Default")
      (node (ref "U$19") (pin "13") (pinfunction "13_13") (pintype "passive"))
      (node (ref "U$19") (pin "13@2") (pinfunction "13_13@2") (pintype "passive"))
      (node (ref "U$19") (pin "13@3") (pinfunction "13_13@3") (pintype "passive"))
    )
    (net (code "257") (name "Net-(U$19-14-Pad14@2)") (class "Default")
      (node (ref "U$19") (pin "14") (pinfunction "14_14") (pintype "passive"))
      (node (ref "U$19") (pin "14@2") (pinfunction "14_14@2") (pintype "passive"))
      (node (ref "U$19") (pin "14@3") (pinfunction "14_14@3") (pintype "passive"))
    )
    (net (code "258") (name "Net-(U$19-15-Pad15@2)") (class "Default")
      (node (ref "U$19") (pin "15") (pinfunction "15_15") (pintype "passive"))
      (node (ref "U$19") (pin "15@2") (pinfunction "15_15@2") (pintype "passive"))
      (node (ref "U$19") (pin "15@3") (pinfunction "15_15@3") (pintype "passive"))
    )
    (net (code "259") (name "Net-(U$19-16-Pad16@2)") (class "Default")
      (node (ref "U$19") (pin "16") (pinfunction "16_16") (pintype "passive"))
      (node (ref "U$19") (pin "16@2") (pinfunction "16_16@2") (pintype "passive"))
      (node (ref "U$19") (pin "16@3") (pinfunction "16_16@3") (pintype "passive"))
    )
    (net (code "260") (name "Net-(U$20-1-Pad1@2)") (class "Default")
      (node (ref "U$20") (pin "1") (pinfunction "1_1") (pintype "passive"))
      (node (ref "U$20") (pin "1@2") (pinfunction "1_1@2") (pintype "passive"))
      (node (ref "U$20") (pin "1@3") (pinfunction "1_1@3") (pintype "passive"))
    )
    (net (code "261") (name "Net-(U$20-2-Pad2@2)") (class "Default")
      (node (ref "U$20") (pin "2") (pinfunction "2_2") (pintype "passive"))
      (node (ref "U$20") (pin "2@2") (pinfunction "2_2@2") (pintype "passive"))
      (node (ref "U$20") (pin "2@3") (pinfunction "2_2@3") (pintype "passive"))
    )
    (net (code "262") (name "Net-(U$20-3-Pad3@2)") (class "Default")
      (node (ref "U$20") (pin "3") (pinfunction "3_3") (pintype "passive"))
      (node (ref "U$20") (pin "3@2") (pinfunction "3_3@2") (pintype "passive"))
      (node (ref "U$20") (pin "3@3") (pinfunction "3_3@3") (pintype "passive"))
    )
    (net (code "263") (name "Net-(U$20-4-Pad4@2)") (class "Default")
      (node (ref "U$20") (pin "4") (pinfunction "4_4") (pintype "passive"))
      (node (ref "U$20") (pin "4@2") (pinfunction "4_4@2") (pintype "passive"))
      (node (ref "U$20") (pin "4@3") (pinfunction "4_4@3") (pintype "passive"))
    )
    (net (code "264") (name "Net-(U$20-5-Pad5@2)") (class "Default")
      (node (ref "U$20") (pin "5") (pinfunction "5_5") (pintype "passive"))
      (node (ref "U$20") (pin "5@2") (pinfunction "5_5@2") (pintype "passive"))
      (node (ref "U$20") (pin "5@3") (pinfunction "5_5@3") (pintype "passive"))
    )
    (net (code "265") (name "Net-(U$20-6-Pad6@2)") (class "Default")
      (node (ref "U$20") (pin "6") (pinfunction "6_6") (pintype "passive"))
      (node (ref "U$20") (pin "6@2") (pinfunction "6_6@2") (pintype "passive"))
      (node (ref "U$20") (pin "6@3") (pinfunction "6_6@3") (pintype "passive"))
    )
    (net (code "266") (name "Net-(U$20-7-Pad7@2)") (class "Default")
      (node (ref "U$20") (pin "7") (pinfunction "7_7") (pintype "passive"))
      (node (ref "U$20") (pin "7@2") (pinfunction "7_7@2") (pintype "passive"))
      (node (ref "U$20") (pin "7@3") (pinfunction "7_7@3") (pintype "passive"))
    )
    (net (code "267") (name "Net-(U$20-8-Pad8@2)") (class "Default")
      (node (ref "U$20") (pin "8") (pinfunction "8_8") (pintype "passive"))
      (node (ref "U$20") (pin "8@2") (pinfunction "8_8@2") (pintype "passive"))
      (node (ref "U$20") (pin "8@3") (pinfunction "8_8@3") (pintype "passive"))
    )
    (net (code "268") (name "Net-(U$20-9-Pad9@2)") (class "Default")
      (node (ref "U$20") (pin "9") (pinfunction "9_9") (pintype "passive"))
      (node (ref "U$20") (pin "9@2") (pinfunction "9_9@2") (pintype "passive"))
      (node (ref "U$20") (pin "9@3") (pinfunction "9_9@3") (pintype "passive"))
    )
    (net (code "269") (name "Net-(U$20-10-Pad10@2)") (class "Default")
      (node (ref "U$20") (pin "10") (pinfunction "10_10") (pintype "passive"))
      (node (ref "U$20") (pin "10@2") (pinfunction "10_10@2") (pintype "passive"))
      (node (ref "U$20") (pin "10@3") (pinfunction "10_10@3") (pintype "passive"))
    )
    (net (code "270") (name "Net-(U$20-11-Pad11@2)") (class "Default")
      (node (ref "U$20") (pin "11") (pinfunction "11_11") (pintype "passive"))
      (node (ref "U$20") (pin "11@2") (pinfunction "11_11@2") (pintype "passive"))
      (node (ref "U$20") (pin "11@3") (pinfunction "11_11@3") (pintype "passive"))
    )
    (net (code "271") (name "Net-(U$20-12-Pad12@2)") (class "Default")
      (node (ref "U$20") (pin "12") (pinfunction "12_12") (pintype "passive"))
      (node (ref "U$20") (pin "12@2") (pinfunction "12_12@2") (pintype "passive"))
      (node (ref "U$20") (pin "12@3") (pinfunction "12_12@3") (pintype "passive"))
    )
    (net (code "272") (name "Net-(U$20-13-Pad13@2)") (class "Default")
      (node (ref "U$20") (pin "13") (pinfunction "13_13") (pintype "passive"))
      (node (ref "U$20") (pin "13@2") (pinfunction "13_13@2") (pintype "passive"))
      (node (ref "U$20") (pin "13@3") (pinfunction "13_13@3") (pintype "passive"))
    )
    (net (code "273") (name "Net-(U$20-14-Pad14@2)") (class "Default")
      (node (ref "U$20") (pin "14") (pinfunction "14_14") (pintype "passive"))
      (node (ref "U$20") (pin "14@2") (pinfunction "14_14@2") (pintype "passive"))
      (node (ref "U$20") (pin "14@3") (pinfunction "14_14@3") (pintype "passive"))
    )
    (net (code "274") (name "Net-(U$20-15-Pad15@2)") (class "Default")
      (node (ref "U$20") (pin "15") (pinfunction "15_15") (pintype "passive"))
      (node (ref "U$20") (pin "15@2") (pinfunction "15_15@2") (pintype "passive"))
      (node (ref "U$20") (pin "15@3") (pinfunction "15_15@3") (pintype "passive"))
    )
    (net (code "275") (name "Net-(U$20-16-Pad16@2)") (class "Default")
      (node (ref "U$20") (pin "16") (pinfunction "16_16") (pintype "passive"))
      (node (ref "U$20") (pin "16@2") (pinfunction "16_16@2") (pintype "passive"))
      (node (ref "U$20") (pin "16@3") (pinfunction "16_16@3") (pintype "passive"))
    )
    (net (code "276") (name "Net-(U$21-1-Pad1@2)") (class "Default")
      (node (ref "U$21") (pin "1") (pinfunction "1_1") (pintype "passive"))
      (node (ref "U$21") (pin "1@2") (pinfunction "1_1@2") (pintype "passive"))
      (node (ref "U$21") (pin "1@3") (pinfunction "1_1@3") (pintype "passive"))
    )
    (net (code "277") (name "Net-(U$21-2-Pad2@2)") (class "Default")
      (node (ref "U$21") (pin "2") (pinfunction "2_2") (pintype "passive"))
      (node (ref "U$21") (pin "2@2") (pinfunction "2_2@2") (pintype "passive"))
      (node (ref "U$21") (pin "2@3") (pinfunction "2_2@3") (pintype "passive"))
    )
    (net (code "278") (name "Net-(U$21-3-Pad3@2)") (class "Default")
      (node (ref "U$21") (pin "3") (pinfunction "3_3") (pintype "passive"))
      (node (ref "U$21") (pin "3@2") (pinfunction "3_3@2") (pintype "passive"))
      (node (ref "U$21") (pin "3@3") (pinfunction "3_3@3") (pintype "passive"))
    )
    (net (code "279") (name "Net-(U$21-4-Pad4@2)") (class "Default")
      (node (ref "U$21") (pin "4") (pinfunction "4_4") (pintype "passive"))
      (node (ref "U$21") (pin "4@2") (pinfunction "4_4@2") (pintype "passive"))
      (node (ref "U$21") (pin "4@3") (pinfunction "4_4@3") (pintype "passive"))
    )
    (net (code "280") (name "Net-(U$21-5-Pad5@2)") (class "Default")
      (node (ref "U$21") (pin "5") (pinfunction "5_5") (pintype "passive"))
      (node (ref "U$21") (pin "5@2") (pinfunction "5_5@2") (pintype "passive"))
      (node (ref "U$21") (pin "5@3") (pinfunction "5_5@3") (pintype "passive"))
    )
    (net (code "281") (name "Net-(U$21-6-Pad6@2)") (class "Default")
      (node (ref "U$21") (pin "6") (pinfunction "6_6") (pintype "passive"))
      (node (ref "U$21") (pin "6@2") (pinfunction "6_6@2") (pintype "passive"))
      (node (ref "U$21") (pin "6@3") (pinfunction "6_6@3") (pintype "passive"))
    )
    (net (code "282") (name "Net-(U$21-7-Pad7@2)") (class "Default")
      (node (ref "U$21") (pin "7") (pinfunction "7_7") (pintype "passive"))
      (node (ref "U$21") (pin "7@2") (pinfunction "7_7@2") (pintype "passive"))
      (node (ref "U$21") (pin "7@3") (pinfunction "7_7@3") (pintype "passive"))
    )
    (net (code "283") (name "Net-(U$21-8-Pad8@2)") (class "Default")
      (node (ref "U$21") (pin "8") (pinfunction "8_8") (pintype "passive"))
      (node (ref "U$21") (pin "8@2") (pinfunction "8_8@2") (pintype "passive"))
      (node (ref "U$21") (pin "8@3") (pinfunction "8_8@3") (pintype "passive"))
    )
    (net (code "284") (name "Net-(U$21-9-Pad9@2)") (class "Default")
      (node (ref "U$21") (pin "9") (pinfunction "9_9") (pintype "passive"))
      (node (ref "U$21") (pin "9@2") (pinfunction "9_9@2") (pintype "passive"))
      (node (ref "U$21") (pin "9@3") (pinfunction "9_9@3") (pintype "passive"))
    )
    (net (code "285") (name "Net-(U$21-10-Pad10@2)") (class "Default")
      (node (ref "U$21") (pin "10") (pinfunction "10_10") (pintype "passive"))
      (node (ref "U$21") (pin "10@2") (pinfunction "10_10@2") (pintype "passive"))
      (node (ref "U$21") (pin "10@3") (pinfunction "10_10@3") (pintype "passive"))
    )
    (net (code "286") (name "Net-(U$21-11-Pad11@2)") (class "Default")
      (node (ref "U$21") (pin "11") (pinfunction "11_11") (pintype "passive"))
      (node (ref "U$21") (pin "11@2") (pinfunction "11_11@2") (pintype "passive"))
      (node (ref "U$21") (pin "11@3") (pinfunction "11_11@3") (pintype "passive"))
    )
    (net (code "287") (name "Net-(U$21-12-Pad12@2)") (class "Default")
      (node (ref "U$21") (pin "12") (pinfunction "12_12") (pintype "passive"))
      (node (ref "U$21") (pin "12@2") (pinfunction "12_12@2") (pintype "passive"))
      (node (ref "U$21") (pin "12@3") (pinfunction "12_12@3") (pintype "passive"))
    )
    (net (code "288") (name "Net-(U$21-13-Pad13@2)") (class "Default")
      (node (ref "U$21") (pin "13") (pinfunction "13_13") (pintype "passive"))
      (node (ref "U$21") (pin "13@2") (pinfunction "13_13@2") (pintype "passive"))
      (node (ref "U$21") (pin "13@3") (pinfunction "13_13@3") (pintype "passive"))
    )
    (net (code "289") (name "Net-(U$21-14-Pad14@2)") (class "Default")
      (node (ref "U$21") (pin "14") (pinfunction "14_14") (pintype "passive"))
      (node (ref "U$21") (pin "14@2") (pinfunction "14_14@2") (pintype "passive"))
      (node (ref "U$21") (pin "14@3") (pinfunction "14_14@3") (pintype "passive"))
    )
    (net (code "290") (name "Net-(U$21-15-Pad15@2)") (class "Default")
      (node (ref "U$21") (pin "15") (pinfunction "15_15") (pintype "passive"))
      (node (ref "U$21") (pin "15@2") (pinfunction "15_15@2") (pintype "passive"))
      (node (ref "U$21") (pin "15@3") (pinfunction "15_15@3") (pintype "passive"))
    )
    (net (code "291") (name "Net-(U$21-16-Pad16@2)") (class "Default")
      (node (ref "U$21") (pin "16") (pinfunction "16_16") (pintype "passive"))
      (node (ref "U$21") (pin "16@2") (pinfunction "16_16@2") (pintype "passive"))
      (node (ref "U$21") (pin "16@3") (pinfunction "16_16@3") (pintype "passive"))
    )
    (net (code "292") (name "Net-(U$22-1-Pad1@2)") (class "Default")
      (node (ref "U$22") (pin "1") (pinfunction "1_1") (pintype "passive"))
      (node (ref "U$22") (pin "1@2") (pinfunction "1_1@2") (pintype "passive"))
      (node (ref "U$22") (pin "1@3") (pinfunction "1_1@3") (pintype "passive"))
    )
    (net (code "293") (name "Net-(U$22-2-Pad2@2)") (class "Default")
      (node (ref "U$22") (pin "2") (pinfunction "2_2") (pintype "passive"))
      (node (ref "U$22") (pin "2@2") (pinfunction "2_2@2") (pintype "passive"))
      (node (ref "U$22") (pin "2@3") (pinfunction "2_2@3") (pintype "passive"))
    )
    (net (code "294") (name "Net-(U$22-3-Pad3@2)") (class "Default")
      (node (ref "U$22") (pin "3") (pinfunction "3_3") (pintype "passive"))
      (node (ref "U$22") (pin "3@2") (pinfunction "3_3@2") (pintype "passive"))
      (node (ref "U$22") (pin "3@3") (pinfunction "3_3@3") (pintype "passive"))
    )
    (net (code "295") (name "Net-(U$22-4-Pad4@2)") (class "Default")
      (node (ref "U$22") (pin "4") (pinfunction "4_4") (pintype "passive"))
      (node (ref "U$22") (pin "4@2") (pinfunction "4_4@2") (pintype "passive"))
      (node (ref "U$22") (pin "4@3") (pinfunction "4_4@3") (pintype "passive"))
    )
    (net (code "296") (name "Net-(U$22-5-Pad5@2)") (class "Default")
      (node (ref "U$22") (pin "5") (pinfunction "5_5") (pintype "passive"))
      (node (ref "U$22") (pin "5@2") (pinfunction "5_5@2") (pintype "passive"))
      (node (ref "U$22") (pin "5@3") (pinfunction "5_5@3") (pintype "passive"))
    )
    (net (code "297") (name "Net-(U$22-6-Pad6@2)") (class "Default")
      (node (ref "U$22") (pin "6") (pinfunction "6_6") (pintype "passive"))
      (node (ref "U$22") (pin "6@2") (pinfunction "6_6@2") (pintype "passive"))
      (node (ref "U$22") (pin "6@3") (pinfunction "6_6@3") (pintype "passive"))
    )
    (net (code "298") (name "Net-(U$22-7-Pad7@2)") (class "Default")
      (node (ref "U$22") (pin "7") (pinfunction "7_7") (pintype "passive"))
      (node (ref "U$22") (pin "7@2") (pinfunction "7_7@2") (pintype "passive"))
      (node (ref "U$22") (pin "7@3") (pinfunction "7_7@3") (pintype "passive"))
    )
    (net (code "299") (name "Net-(U$22-8-Pad8@2)") (class "Default")
      (node (ref "U$22") (pin "8") (pinfunction "8_8") (pintype "passive"))
      (node (ref "U$22") (pin "8@2") (pinfunction "8_8@2") (pintype "passive"))
      (node (ref "U$22") (pin "8@3") (pinfunction "8_8@3") (pintype "passive"))
    )
    (net (code "300") (name "Net-(U$22-9-Pad9@2)") (class "Default")
      (node (ref "U$22") (pin "9") (pinfunction "9_9") (pintype "passive"))
      (node (ref "U$22") (pin "9@2") (pinfunction "9_9@2") (pintype "passive"))
      (node (ref "U$22") (pin "9@3") (pinfunction "9_9@3") (pintype "passive"))
    )
    (net (code "301") (name "Net-(U$22-10-Pad10@2)") (class "Default")
      (node (ref "U$22") (pin "10") (pinfunction "10_10") (pintype "passive"))
      (node (ref "U$22") (pin "10@2") (pinfunction "10_10@2") (pintype "passive"))
      (node (ref "U$22") (pin "10@3") (pinfunction "10_10@3") (pintype "passive"))
    )
    (net (code "302") (name "Net-(U$22-11-Pad11@2)") (class "Default")
      (node (ref "U$22") (pin "11") (pinfunction "11_11") (pintype "passive"))
      (node (ref "U$22") (pin "11@2") (pinfunction "11_11@2") (pintype "passive"))
      (node (ref "U$22") (pin "11@3") (pinfunction "11_11@3") (pintype "passive"))
    )
    (net (code "303") (name "Net-(U$22-12-Pad12@2)") (class "Default")
      (node (ref "U$22") (pin "12") (pinfunction "12_12") (pintype "passive"))
      (node (ref "U$22") (pin "12@2") (pinfunction "12_12@2") (pintype "passive"))
      (node (ref "U$22") (pin "12@3") (pinfunction "12_12@3") (pintype "passive"))
    )
    (net (code "304") (name "Net-(U$22-13-Pad13@2)") (class "Default")
      (node (ref "U$22") (pin "13") (pinfunction "13_13") (pintype "passive"))
      (node (ref "U$22") (pin "13@2") (pinfunction "13_13@2") (pintype "passive"))
      (node (ref "U$22") (pin "13@3") (pinfunction "13_13@3") (pintype "passive"))
    )
    (net (code "305") (name "Net-(U$22-14-Pad14@2)") (class "Default")
      (node (ref "U$22") (pin "14") (pinfunction "14_14") (pintype "passive"))
      (node (ref "U$22") (pin "14@2") (pinfunction "14_14@2") (pintype "passive"))
      (node (ref "U$22") (pin "14@3") (pinfunction "14_14@3") (pintype "passive"))
    )
    (net (code "306") (name "Net-(U$22-15-Pad15@2)") (class "Default")
      (node (ref "U$22") (pin "15") (pinfunction "15_15") (pintype "passive"))
      (node (ref "U$22") (pin "15@2") (pinfunction "15_15@2") (pintype "passive"))
      (node (ref "U$22") (pin "15@3") (pinfunction "15_15@3") (pintype "passive"))
    )
    (net (code "307") (name "Net-(U$22-16-Pad16@2)") (class "Default")
      (node (ref "U$22") (pin "16") (pinfunction "16_16") (pintype "passive"))
      (node (ref "U$22") (pin "16@2") (pinfunction "16_16@2") (pintype "passive"))
      (node (ref "U$22") (pin "16@3") (pinfunction "16_16@3") (pintype "passive"))
    )
    (net (code "308") (name "Net-(U$23-1-Pad1@2)") (class "Default")
      (node (ref "U$23") (pin "1") (pinfunction "1_1") (pintype "passive"))
      (node (ref "U$23") (pin "1@2") (pinfunction "1_1@2") (pintype "passive"))
      (node (ref "U$23") (pin "1@3") (pinfunction "1_1@3") (pintype "passive"))
    )
    (net (code "309") (name "Net-(U$23-2-Pad2@2)") (class "Default")
      (node (ref "U$23") (pin "2") (pinfunction "2_2") (pintype "passive"))
      (node (ref "U$23") (pin "2@2") (pinfunction "2_2@2") (pintype "passive"))
      (node (ref "U$23") (pin "2@3") (pinfunction "2_2@3") (pintype "passive"))
    )
    (net (code "310") (name "Net-(U$23-3-Pad3@2)") (class "Default")
      (node (ref "U$23") (pin "3") (pinfunction "3_3") (pintype "passive"))
      (node (ref "U$23") (pin "3@2") (pinfunction "3_3@2") (pintype "passive"))
      (node (ref "U$23") (pin "3@3") (pinfunction "3_3@3") (pintype "passive"))
    )
    (net (code "311") (name "Net-(U$23-4-Pad4@2)") (class "Default")
      (node (ref "U$23") (pin "4") (pinfunction "4_4") (pintype "passive"))
      (node (ref "U$23") (pin "4@2") (pinfunction "4_4@2") (pintype "passive"))
      (node (ref "U$23") (pin "4@3") (pinfunction "4_4@3") (pintype "passive"))
    )
    (net (code "312") (name "Net-(U$23-5-Pad5@2)") (class "Default")
      (node (ref "U$23") (pin "5") (pinfunction "5_5") (pintype "passive"))
      (node (ref "U$23") (pin "5@2") (pinfunction "5_5@2") (pintype "passive"))
      (node (ref "U$23") (pin "5@3") (pinfunction "5_5@3") (pintype "passive"))
    )
    (net (code "313") (name "Net-(U$23-6-Pad6@2)") (class "Default")
      (node (ref "U$23") (pin "6") (pinfunction "6_6") (pintype "passive"))
      (node (ref "U$23") (pin "6@2") (pinfunction "6_6@2") (pintype "passive"))
      (node (ref "U$23") (pin "6@3") (pinfunction "6_6@3") (pintype "passive"))
    )
    (net (code "314") (name "Net-(U$23-7-Pad7@2)") (class "Default")
      (node (ref "U$23") (pin "7") (pinfunction "7_7") (pintype "passive"))
      (node (ref "U$23") (pin "7@2") (pinfunction "7_7@2") (pintype "passive"))
      (node (ref "U$23") (pin "7@3") (pinfunction "7_7@3") (pintype "passive"))
    )
    (net (code "315") (name "Net-(U$23-8-Pad8@2)") (class "Default")
      (node (ref "U$23") (pin "8") (pinfunction "8_8") (pintype "passive"))
      (node (ref "U$23") (pin "8@2") (pinfunction "8_8@2") (pintype "passive"))
      (node (ref "U$23") (pin "8@3") (pinfunction "8_8@3") (pintype "passive"))
    )
    (net (code "316") (name "Net-(U$23-9-Pad9@2)") (class "Default")
      (node (ref "U$23") (pin "9") (pinfunction "9_9") (pintype "passive"))
      (node (ref "U$23") (pin "9@2") (pinfunction "9_9@2") (pintype "passive"))
      (node (ref "U$23") (pin "9@3") (pinfunction "9_9@3") (pintype "passive"))
    )
    (net (code "317") (name "Net-(U$23-10-Pad10@2)") (class "Default")
      (node (ref "U$23") (pin "10") (pinfunction "10_10") (pintype "passive"))
      (node (ref "U$23") (pin "10@2") (pinfunction "10_10@2") (pintype "passive"))
      (node (ref "U$23") (pin "10@3") (pinfunction "10_10@3") (pintype "passive"))
    )
    (net (code "318") (name "Net-(U$23-11-Pad11@2)") (class "Default")
      (node (ref "U$23") (pin "11") (pinfunction "11_11") (pintype "passive"))
      (node (ref "U$23") (pin "11@2") (pinfunction "11_11@2") (pintype "passive"))
      (node (ref "U$23") (pin "11@3") (pinfunction "11_11@3") (pintype "passive"))
    )
    (net (code "319") (name "Net-(U$23-12-Pad12@2)") (class "Default")
      (node (ref "U$23") (pin "12") (pinfunction "12_12") (pintype "passive"))
      (node (ref "U$23") (pin "12@2") (pinfunction "12_12@2") (pintype "passive"))
      (node (ref "U$23") (pin "12@3") (pinfunction "12_12@3") (pintype "passive"))
    )
    (net (code "320") (name "Net-(U$23-13-Pad13@2)") (class "Default")
      (node (ref "U$23") (pin "13") (pinfunction "13_13") (pintype "passive"))
      (node (ref "U$23") (pin "13@2") (pinfunction "13_13@2") (pintype "passive"))
      (node (ref "U$23") (pin "13@3") (pinfunction "13_13@3") (pintype "passive"))
    )
    (net (code "321") (name "Net-(U$23-14-Pad14@2)") (class "Default")
      (node (ref "U$23") (pin "14") (pinfunction "14_14") (pintype "passive"))
      (node (ref "U$23") (pin "14@2") (pinfunction "14_14@2") (pintype "passive"))
      (node (ref "U$23") (pin "14@3") (pinfunction "14_14@3") (pintype "passive"))
    )
    (net (code "322") (name "Net-(U$23-15-Pad15@2)") (class "Default")
      (node (ref "U$23") (pin "15") (pinfunction "15_15") (pintype "passive"))
      (node (ref "U$23") (pin "15@2") (pinfunction "15_15@2") (pintype "passive"))
      (node (ref "U$23") (pin "15@3") (pinfunction "15_15@3") (pintype "passive"))
    )
    (net (code "323") (name "Net-(U$23-16-Pad16@2)") (class "Default")
      (node (ref "U$23") (pin "16") (pinfunction "16_16") (pintype "passive"))
      (node (ref "U$23") (pin "16@2") (pinfunction "16_16@2") (pintype "passive"))
      (node (ref "U$23") (pin "16@3") (pinfunction "16_16@3") (pintype "passive"))
    )
    (net (code "324") (name "Net-(U$26A-P$1)") (class "Default")
      (node (ref "U$26") (pin "A1") (pinfunction "P$1_A1") (pintype "passive"))
      (node (ref "U$6") (pin "A1") (pinfunction "1_A1") (pintype "bidirectional"))
    )
    (net (code "325") (name "Net-(U$26B-P$1)") (class "Default")
      (node (ref "U$26") (pin "B1") (pinfunction "P$1_B1") (pintype "passive"))
      (node (ref "U$6") (pin "B1") (pinfunction "1_B1") (pintype "bidirectional"))
    )
    (net (code "326") (name "Net-(U$26C-P$1)") (class "Default")
      (node (ref "U$26") (pin "C1") (pinfunction "P$1_C1") (pintype "passive"))
      (node (ref "U$6") (pin "C1") (pinfunction "1_C1") (pintype "bidirectional"))
    )
    (net (code "327") (name "Net-(U$26D-P$1)") (class "Default")
      (node (ref "U$26") (pin "D1") (pinfunction "P$1_D1") (pintype "passive"))
      (node (ref "U$6") (pin "D1") (pinfunction "1_D1") (pintype "bidirectional"))
    )
    (net (code "328") (name "Net-(U$26E-P$1)") (class "Default")
      (node (ref "U$26") (pin "E1") (pinfunction "P$1_E1") (pintype "passive"))
      (node (ref "U$6") (pin "E1") (pinfunction "1_E1") (pintype "bidirectional"))
    )
    (net (code "329") (name "Net-(U$26F-P$1)") (class "Default")
      (node (ref "U$26") (pin "F1") (pinfunction "P$1_F1") (pintype "passive"))
      (node (ref "U$6") (pin "F1") (pinfunction "1_F1") (pintype "bidirectional"))
    )
    (net (code "330") (name "Net-(U$26G-P$1)") (class "Default")
      (node (ref "U$26") (pin "H1") (pinfunction "P$1_H1") (pintype "passive"))
      (node (ref "U$6") (pin "H1") (pinfunction "1_H1") (pintype "bidirectional"))
    )
    (net (code "331") (name "Net-(U$26H-P$1)") (class "Default")
      (node (ref "U$26") (pin "J1") (pinfunction "P$1_J1") (pintype "passive"))
      (node (ref "U$6") (pin "J1") (pinfunction "1_J1") (pintype "bidirectional"))
    )
    (net (code "332") (name "Net-(U$26I-P$1)") (class "Default")
      (node (ref "U$26") (pin "K1") (pinfunction "P$1_K1") (pintype "passive"))
      (node (ref "U$6") (pin "K1") (pinfunction "1_K1") (pintype "bidirectional"))
    )
    (net (code "333") (name "Net-(U$26J-P$1)") (class "Default")
      (node (ref "U$26") (pin "L1") (pinfunction "P$1_L1") (pintype "passive"))
      (node (ref "U$6") (pin "L1") (pinfunction "1_L1") (pintype "bidirectional"))
    )
    (net (code "334") (name "Net-(U$26K-P$1)") (class "Default")
      (node (ref "U$26") (pin "M1") (pinfunction "P$1_M1") (pintype "passive"))
      (node (ref "U$6") (pin "M1") (pinfunction "1_M1") (pintype "bidirectional"))
    )
    (net (code "335") (name "Net-(U$26L-P$1)") (class "Default")
      (node (ref "U$26") (pin "N1") (pinfunction "P$1_N1") (pintype "passive"))
      (node (ref "U$6") (pin "N1") (pinfunction "1_N1") (pintype "bidirectional"))
    )
    (net (code "336") (name "Net-(U$26M-P$1)") (class "Default")
      (node (ref "U$26") (pin "P1") (pinfunction "P$1_P1") (pintype "passive"))
      (node (ref "U$6") (pin "P1") (pinfunction "1_P1") (pintype "bidirectional"))
    )
    (net (code "337") (name "Net-(U$26N-P$1)") (class "Default")
      (node (ref "U$26") (pin "R1") (pinfunction "P$1_R1") (pintype "passive"))
      (node (ref "U$6") (pin "R1") (pinfunction "1_R1") (pintype "bidirectional"))
    )
    (net (code "338") (name "Net-(U$26O-P$1)") (class "Default")
      (node (ref "U$26") (pin "S1") (pinfunction "P$1_S1") (pintype "passive"))
      (node (ref "U$6") (pin "S1") (pinfunction "1_S1") (pintype "bidirectional"))
    )
    (net (code "339") (name "Net-(U$26Q-P$1)") (class "Default")
      (node (ref "U$26") (pin "U1") (pinfunction "P$1_U1") (pintype "passive"))
      (node (ref "U$6") (pin "U1") (pinfunction "1_U1") (pintype "bidirectional"))
    )
    (net (code "340") (name "Net-(U$26R-P$1)") (class "Default")
      (node (ref "U$26") (pin "V1") (pinfunction "P$1_V1") (pintype "passive"))
      (node (ref "U$6") (pin "V1") (pinfunction "1_V1") (pintype "bidirectional"))
    )
    (net (code "341") (name "Net-(U$27B-P$1)") (class "Default")
      (node (ref "U$27") (pin "B1") (pinfunction "P$1_B1") (pintype "passive"))
      (node (ref "U$6") (pin "B2") (pinfunction "1_B2") (pintype "bidirectional"))
    )
    (net (code "342") (name "Net-(U$27D-P$1)") (class "Default")
      (node (ref "U$27") (pin "D1") (pinfunction "P$1_D1") (pintype "passive"))
      (node (ref "U$6") (pin "D2") (pinfunction "1_D2") (pintype "bidirectional"))
    )
    (net (code "343") (name "Net-(U$27E-P$1)") (class "Default")
      (node (ref "U$27") (pin "E1") (pinfunction "P$1_E1") (pintype "passive"))
      (node (ref "U$6") (pin "E2") (pinfunction "1_E2") (pintype "bidirectional"))
    )
    (net (code "344") (name "Net-(U$27F-P$1)") (class "Default")
      (node (ref "U$27") (pin "F1") (pinfunction "P$1_F1") (pintype "passive"))
      (node (ref "U$6") (pin "F2") (pinfunction "1_F2") (pintype "bidirectional"))
    )
    (net (code "345") (name "Net-(U$27G-P$1)") (class "Default")
      (node (ref "U$27") (pin "H1") (pinfunction "P$1_H1") (pintype "passive"))
      (node (ref "U$6") (pin "H2") (pinfunction "1_H2") (pintype "bidirectional"))
    )
    (net (code "346") (name "Net-(U$27H-P$1)") (class "Default")
      (node (ref "U$27") (pin "J1") (pinfunction "P$1_J1") (pintype "passive"))
      (node (ref "U$6") (pin "J2") (pinfunction "1_J2") (pintype "bidirectional"))
    )
    (net (code "347") (name "Net-(U$27I-P$1)") (class "Default")
      (node (ref "U$27") (pin "K1") (pinfunction "P$1_K1") (pintype "passive"))
      (node (ref "U$6") (pin "K2") (pinfunction "1_K2") (pintype "bidirectional"))
    )
    (net (code "348") (name "Net-(U$27J-P$1)") (class "Default")
      (node (ref "U$27") (pin "L1") (pinfunction "P$1_L1") (pintype "passive"))
      (node (ref "U$6") (pin "L2") (pinfunction "1_L2") (pintype "bidirectional"))
    )
    (net (code "349") (name "Net-(U$27K-P$1)") (class "Default")
      (node (ref "U$27") (pin "M1") (pinfunction "P$1_M1") (pintype "passive"))
      (node (ref "U$6") (pin "M2") (pinfunction "1_M2") (pintype "bidirectional"))
    )
    (net (code "350") (name "Net-(U$27L-P$1)") (class "Default")
      (node (ref "U$27") (pin "N1") (pinfunction "P$1_N1") (pintype "passive"))
      (node (ref "U$6") (pin "N2") (pinfunction "1_N2") (pintype "bidirectional"))
    )
    (net (code "351") (name "Net-(U$27M-P$1)") (class "Default")
      (node (ref "U$27") (pin "P1") (pinfunction "P$1_P1") (pintype "passive"))
      (node (ref "U$6") (pin "P2") (pinfunction "1_P2") (pintype "bidirectional"))
    )
    (net (code "352") (name "Net-(U$27N-P$1)") (class "Default")
      (node (ref "U$27") (pin "R1") (pinfunction "P$1_R1") (pintype "passive"))
      (node (ref "U$6") (pin "R2") (pinfunction "1_R2") (pintype "bidirectional"))
    )
    (net (code "353") (name "Net-(U$27O-P$1)") (class "Default")
      (node (ref "U$27") (pin "S1") (pinfunction "P$1_S1") (pintype "passive"))
      (node (ref "U$6") (pin "S2") (pinfunction "1_S2") (pintype "bidirectional"))
    )
    (net (code "354") (name "Net-(U$27P-P$1)") (class "Default")
      (node (ref "U$27") (pin "T1") (pinfunction "P$1_T1") (pintype "passive"))
      (node (ref "U$6") (pin "T2") (pinfunction "1_T2") (pintype "bidirectional"))
    )
    (net (code "355") (name "Net-(U$27Q-P$1)") (class "Default")
      (node (ref "U$27") (pin "U1") (pinfunction "P$1_U1") (pintype "passive"))
      (node (ref "U$6") (pin "U2") (pinfunction "1_U2") (pintype "bidirectional"))
    )
    (net (code "356") (name "Net-(U$27R-P$1)") (class "Default")
      (node (ref "U$27") (pin "V1") (pinfunction "P$1_V1") (pintype "passive"))
      (node (ref "U$6") (pin "V2") (pinfunction "1_V2") (pintype "bidirectional"))
    )
  )
)
